# 09_FPGA_misc.net
KiCad netlist of a schematic drawn in Altium Designer
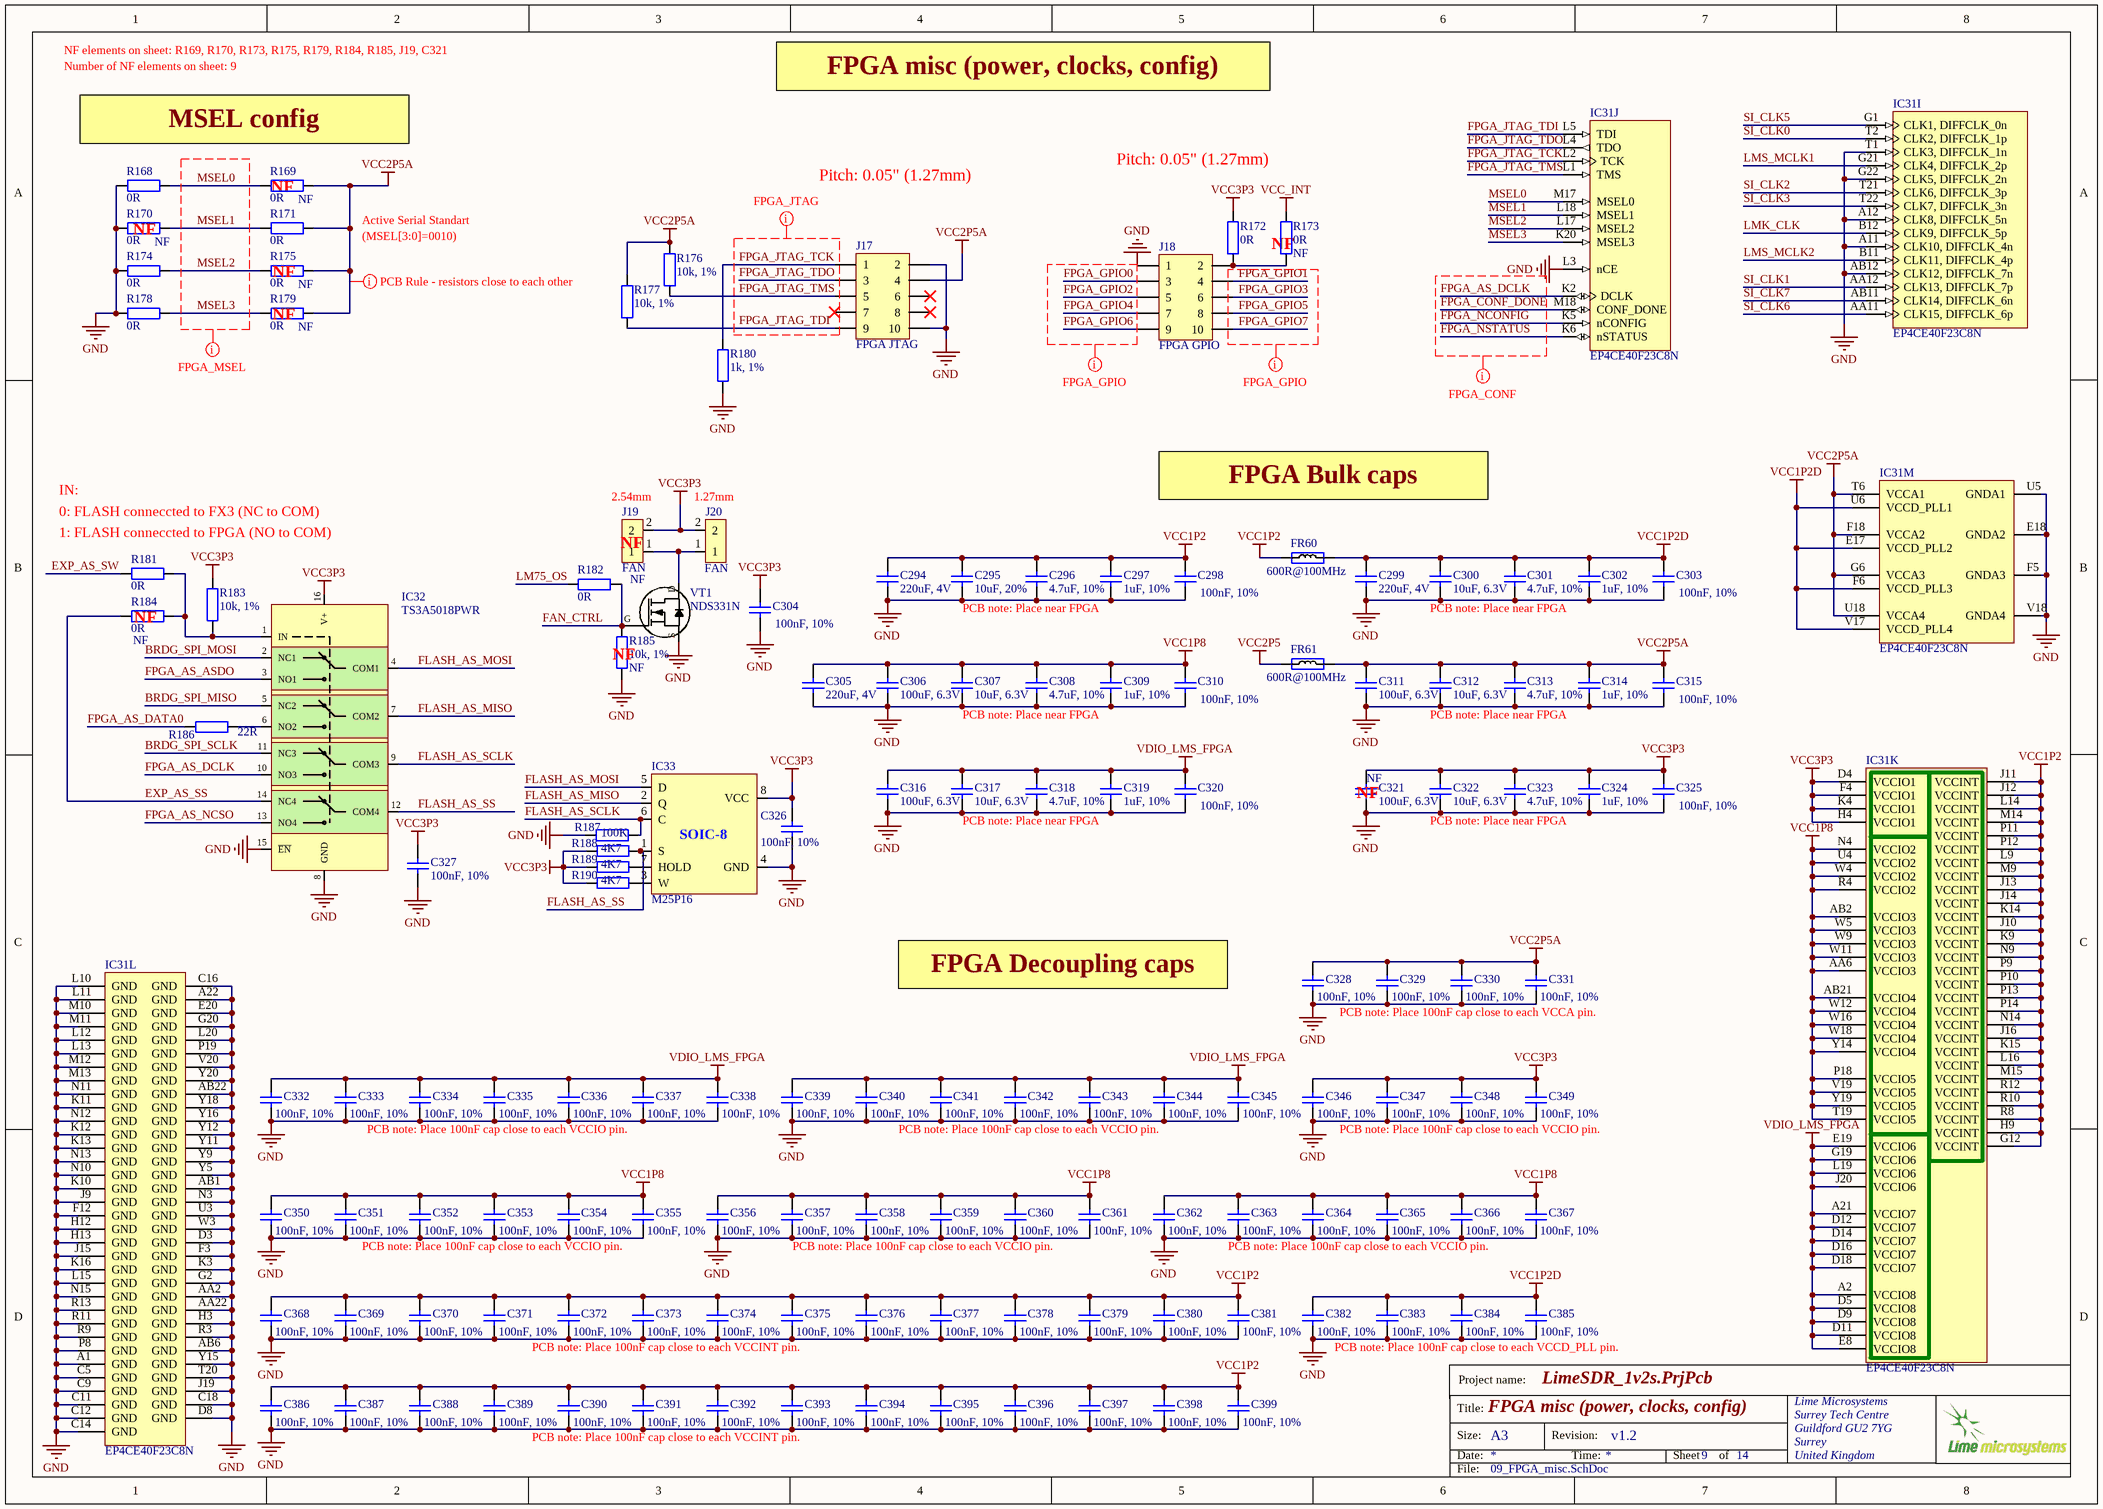
[diagram p0: 09_FPGA_misc.SchDoc]

(export (version "E")
  (design (tool "Eeschema 10.0.6"))
  (components
    (comp (ref "C294")
      (value "220uF, 4V")
      (footprint "LimeMicroAltiumLib_pcbLib:CAP1206")
      (fields
        (field (name "MANUFACTURER PART NUMBER") "GRM31CR60G227ME11L")
        (field (name "MANUFACTURER") "Murata Electronics North America")
        (field (name "TOLERANCE") "±20%")
      )
      (libsource (lib "LimeFPGAboard_schLib") (part "Cap_1206"))
    )
    (comp (ref "C295")
      (value "10uF, 20%")
      (footprint "CAP0603")
      (fields (field (name "MANUFACTURER") "Yageo") (field (name "TOLERANCE") "±20%"))
      (libsource (lib "LimeMicroAltiumLib_schLib") (part "Cap_0603"))
    )
    (comp (ref "C296")
      (value "4.7uF, 10%")
      (footprint "CAP0603")
      (fields (field (name "TOLERANCE") "10 %"))
      (libsource (lib "LimeFPGAboard_schLib") (part "Cap_0603"))
    )
    (comp (ref "C297")
      (value "1uF, 10%")
      (footprint "CAP0402")
      (fields (field (name "MANUFACTURER") "TDK"))
      (libsource (lib "LimeMicroAltiumLib_schLib") (part "Cap_0402"))
    )
    (comp (ref "C298")
      (value "100nF, 10%")
      (footprint "CAP0402")
      (fields
        (field (name "TOLERANCE") "10 %")
        (field (name "MANUFACTURER") "Murata Electronics")
        (field (name "MANUFACTURER PART NUMBER") "GRM155R71C104KA88D")
      )
      (libsource (lib "LimeFPGAboard_schLib") (part "Cap_0603"))
    )
    (comp (ref "C299")
      (value "220uF, 4V")
      (footprint "LimeMicroAltiumLib_pcbLib:CAP1206")
      (fields
        (field (name "MANUFACTURER PART NUMBER") "GRM31CR60G227ME11L")
        (field (name "MANUFACTURER") "Murata Electronics North America")
        (field (name "TOLERANCE") "±20%")
      )
      (libsource (lib "LimeFPGAboard_schLib") (part "Cap_1206"))
    )
    (comp (ref "C300")
      (value "10uF, 6.3V")
      (footprint "CAP0603")
      (fields (field (name "TOLERANCE") "±20%") (field (name "MANUFACTURER") "Yageo"))
      (libsource (lib "LimeFPGAboard_schLib") (part "Cap_0603"))
    )
    (comp (ref "C301")
      (value "4.7uF, 10%")
      (footprint "CAP0603")
      (fields (field (name "TOLERANCE") "10 %"))
      (libsource (lib "LimeFPGAboard_schLib") (part "Cap_0603"))
    )
    (comp (ref "C302")
      (value "1uF, 10%")
      (footprint "CAP0402")
      (fields (field (name "MANUFACTURER") "TDK"))
      (libsource (lib "LimeMicroAltiumLib_schLib") (part "Cap_0402"))
    )
    (comp (ref "C303")
      (value "100nF, 10%")
      (footprint "CAP0402")
      (fields
        (field (name "TOLERANCE") "10 %")
        (field (name "MANUFACTURER") "Murata Electronics")
        (field (name "MANUFACTURER PART NUMBER") "GRM155R71C104KA88D")
      )
      (libsource (lib "LimeFPGAboard_schLib") (part "Cap_0603"))
    )
    (comp (ref "C304")
      (value "100nF, 10%")
      (footprint "CAP0402")
      (fields
        (field (name "TOLERANCE") "10 %")
        (field (name "MANUFACTURER") "Murata Electronics")
        (field (name "MANUFACTURER PART NUMBER") "GRM155R71C104KA88D")
      )
      (libsource (lib "LimeFPGAboard_schLib") (part "Cap_0603"))
    )
    (comp (ref "C305")
      (value "220uF, 4V")
      (footprint "LimeMicroAltiumLib_pcbLib:CAP1206")
      (fields
        (field (name "MANUFACTURER PART NUMBER") "GRM31CR60G227ME11L")
        (field (name "MANUFACTURER") "Murata Electronics North America")
        (field (name "TOLERANCE") "±20%")
      )
      (libsource (lib "LimeFPGAboard_schLib") (part "Cap_1206"))
    )
    (comp (ref "C306")
      (value "100uF, 6.3V")
      (footprint "CAP1206")
      (fields (field (name "MANUFACTURER") "MURATA"))
      (libsource (lib "LimeFPGAboard_schLib") (part "Cap_1206"))
    )
    (comp (ref "C307")
      (value "10uF, 6.3V")
      (footprint "CAP0603")
      (fields (field (name "TOLERANCE") "±20%") (field (name "MANUFACTURER") "Yageo"))
      (libsource (lib "LimeFPGAboard_schLib") (part "Cap_0603"))
    )
    (comp (ref "C308")
      (value "4.7uF, 10%")
      (footprint "CAP0603")
      (fields (field (name "TOLERANCE") "10 %"))
      (libsource (lib "LimeFPGAboard_schLib") (part "Cap_0603"))
    )
    (comp (ref "C309")
      (value "1uF, 10%")
      (footprint "CAP0402")
      (fields (field (name "MANUFACTURER") "TDK"))
      (libsource (lib "LimeMicroAltiumLib_schLib") (part "Cap_0402"))
    )
    (comp (ref "C310")
      (value "100nF, 10%")
      (footprint "CAP0402")
      (fields
        (field (name "TOLERANCE") "10 %")
        (field (name "MANUFACTURER") "Murata Electronics")
        (field (name "MANUFACTURER PART NUMBER") "GRM155R71C104KA88D")
      )
      (libsource (lib "LimeFPGAboard_schLib") (part "Cap_0603"))
    )
    (comp (ref "C311")
      (value "100uF, 6.3V")
      (footprint "CAP1206")
      (fields (field (name "MANUFACTURER") "MURATA"))
      (libsource (lib "LimeFPGAboard_schLib") (part "Cap_1206"))
    )
    (comp (ref "C312")
      (value "10uF, 6.3V")
      (footprint "CAP0603")
      (fields (field (name "TOLERANCE") "±20%") (field (name "MANUFACTURER") "Yageo"))
      (libsource (lib "LimeFPGAboard_schLib") (part "Cap_0603"))
    )
    (comp (ref "C313")
      (value "4.7uF, 10%")
      (footprint "CAP0603")
      (fields (field (name "TOLERANCE") "10 %"))
      (libsource (lib "LimeFPGAboard_schLib") (part "Cap_0603"))
    )
    (comp (ref "C314")
      (value "1uF, 10%")
      (footprint "CAP0402")
      (fields (field (name "MANUFACTURER") "TDK"))
      (libsource (lib "LimeMicroAltiumLib_schLib") (part "Cap_0402"))
    )
    (comp (ref "C315")
      (value "100nF, 10%")
      (footprint "CAP0402")
      (fields
        (field (name "TOLERANCE") "10 %")
        (field (name "MANUFACTURER") "Murata Electronics")
        (field (name "MANUFACTURER PART NUMBER") "GRM155R71C104KA88D")
      )
      (libsource (lib "LimeFPGAboard_schLib") (part "Cap_0603"))
    )
    (comp (ref "C316")
      (value "100uF, 6.3V")
      (footprint "CAP1206")
      (fields (field (name "MANUFACTURER") "MURATA"))
      (libsource (lib "LimeFPGAboard_schLib") (part "Cap_1206"))
    )
    (comp (ref "C317")
      (value "10uF, 6.3V")
      (footprint "CAP0603")
      (fields (field (name "TOLERANCE") "±20%") (field (name "MANUFACTURER") "Yageo"))
      (libsource (lib "LimeFPGAboard_schLib") (part "Cap_0603"))
    )
    (comp (ref "C318")
      (value "4.7uF, 10%")
      (footprint "CAP0603")
      (fields (field (name "TOLERANCE") "10 %"))
      (libsource (lib "LimeFPGAboard_schLib") (part "Cap_0603"))
    )
    (comp (ref "C319")
      (value "1uF, 10%")
      (footprint "CAP0402")
      (fields (field (name "MANUFACTURER") "TDK"))
      (libsource (lib "LimeMicroAltiumLib_schLib") (part "Cap_0402"))
    )
    (comp (ref "C320")
      (value "100nF, 10%")
      (footprint "CAP0402")
      (fields
        (field (name "TOLERANCE") "10 %")
        (field (name "MANUFACTURER") "Murata Electronics")
        (field (name "MANUFACTURER PART NUMBER") "GRM155R71C104KA88D")
      )
      (libsource (lib "LimeFPGAboard_schLib") (part "Cap_0603"))
    )
    (comp (ref "C321")
      (value "100uF, 6.3V")
      (footprint "CAP1206")
      (fields (field (name "MANUFACTURER") "MURATA") (field (name "ASSEMBLY INFO") "NF"))
      (libsource (lib "LimeFPGAboard_schLib") (part "Cap_1206"))
    )
    (comp (ref "C322")
      (value "10uF, 6.3V")
      (footprint "CAP0603")
      (fields (field (name "TOLERANCE") "±20%") (field (name "MANUFACTURER") "Yageo"))
      (libsource (lib "LimeFPGAboard_schLib") (part "Cap_0603"))
    )
    (comp (ref "C323")
      (value "4.7uF, 10%")
      (footprint "CAP0603")
      (fields (field (name "TOLERANCE") "10 %"))
      (libsource (lib "LimeFPGAboard_schLib") (part "Cap_0603"))
    )
    (comp (ref "C324")
      (value "1uF, 10%")
      (footprint "CAP0402")
      (fields (field (name "MANUFACTURER") "TDK"))
      (libsource (lib "LimeMicroAltiumLib_schLib") (part "Cap_0402"))
    )
    (comp (ref "C325")
      (value "100nF, 10%")
      (footprint "CAP0402")
      (fields
        (field (name "TOLERANCE") "10 %")
        (field (name "MANUFACTURER") "Murata Electronics")
        (field (name "MANUFACTURER PART NUMBER") "GRM155R71C104KA88D")
      )
      (libsource (lib "LimeFPGAboard_schLib") (part "Cap_0603"))
    )
    (comp (ref "C326")
      (value "100nF, 10%")
      (footprint "CAP0402")
      (fields
        (field (name "TOLERANCE") "10 %")
        (field (name "MANUFACTURER") "Murata Electronics")
        (field (name "MANUFACTURER PART NUMBER") "GRM155R71C104KA88D")
      )
      (libsource (lib "LimeFPGAboard_schLib") (part "Cap_0603"))
    )
    (comp (ref "C327")
      (value "100nF, 10%")
      (footprint "CAP0402")
      (fields
        (field (name "TOLERANCE") "10 %")
        (field (name "MANUFACTURER") "Murata Electronics")
        (field (name "MANUFACTURER PART NUMBER") "GRM155R71C104KA88D")
      )
      (libsource (lib "LimeFPGAboard_schLib") (part "Cap_0603"))
    )
    (comp (ref "C328")
      (value "100nF, 10%")
      (footprint "CAP0402")
      (fields
        (field (name "TOLERANCE") "10 %")
        (field (name "MANUFACTURER") "Murata Electronics")
        (field (name "MANUFACTURER PART NUMBER") "GRM155R71C104KA88D")
      )
      (libsource (lib "LimeFPGAboard_schLib") (part "Cap_0603"))
    )
    (comp (ref "C329")
      (value "100nF, 10%")
      (footprint "CAP0402")
      (fields
        (field (name "TOLERANCE") "10 %")
        (field (name "MANUFACTURER") "Murata Electronics")
        (field (name "MANUFACTURER PART NUMBER") "GRM155R71C104KA88D")
      )
      (libsource (lib "LimeFPGAboard_schLib") (part "Cap_0603"))
    )
    (comp (ref "C330")
      (value "100nF, 10%")
      (footprint "CAP0402")
      (fields
        (field (name "TOLERANCE") "10 %")
        (field (name "MANUFACTURER") "Murata Electronics")
        (field (name "MANUFACTURER PART NUMBER") "GRM155R71C104KA88D")
      )
      (libsource (lib "LimeFPGAboard_schLib") (part "Cap_0603"))
    )
    (comp (ref "C331")
      (value "100nF, 10%")
      (footprint "CAP0402")
      (fields
        (field (name "TOLERANCE") "10 %")
        (field (name "MANUFACTURER") "Murata Electronics")
        (field (name "MANUFACTURER PART NUMBER") "GRM155R71C104KA88D")
      )
      (libsource (lib "LimeFPGAboard_schLib") (part "Cap_0603"))
    )
    (comp (ref "C332")
      (value "100nF, 10%")
      (footprint "CAP0402")
      (fields
        (field (name "TOLERANCE") "10 %")
        (field (name "MANUFACTURER") "Murata Electronics")
        (field (name "MANUFACTURER PART NUMBER") "GRM155R71C104KA88D")
      )
      (libsource (lib "LimeFPGAboard_schLib") (part "Cap_0603"))
    )
    (comp (ref "C333")
      (value "100nF, 10%")
      (footprint "CAP0402")
      (fields
        (field (name "TOLERANCE") "10 %")
        (field (name "MANUFACTURER") "Murata Electronics")
        (field (name "MANUFACTURER PART NUMBER") "GRM155R71C104KA88D")
      )
      (libsource (lib "LimeFPGAboard_schLib") (part "Cap_0603"))
    )
    (comp (ref "C334")
      (value "100nF, 10%")
      (footprint "CAP0402")
      (fields
        (field (name "TOLERANCE") "10 %")
        (field (name "MANUFACTURER") "Murata Electronics")
        (field (name "MANUFACTURER PART NUMBER") "GRM155R71C104KA88D")
      )
      (libsource (lib "LimeFPGAboard_schLib") (part "Cap_0603"))
    )
    (comp (ref "C335")
      (value "100nF, 10%")
      (footprint "CAP0402")
      (fields
        (field (name "TOLERANCE") "10 %")
        (field (name "MANUFACTURER") "Murata Electronics")
        (field (name "MANUFACTURER PART NUMBER") "GRM155R71C104KA88D")
      )
      (libsource (lib "LimeFPGAboard_schLib") (part "Cap_0603"))
    )
    (comp (ref "C336")
      (value "100nF, 10%")
      (footprint "CAP0402")
      (fields
        (field (name "TOLERANCE") "10 %")
        (field (name "MANUFACTURER") "Murata Electronics")
        (field (name "MANUFACTURER PART NUMBER") "GRM155R71C104KA88D")
      )
      (libsource (lib "LimeFPGAboard_schLib") (part "Cap_0603"))
    )
    (comp (ref "C337")
      (value "100nF, 10%")
      (footprint "CAP0402")
      (fields
        (field (name "TOLERANCE") "10 %")
        (field (name "MANUFACTURER") "Murata Electronics")
        (field (name "MANUFACTURER PART NUMBER") "GRM155R71C104KA88D")
      )
      (libsource (lib "LimeFPGAboard_schLib") (part "Cap_0603"))
    )
    (comp (ref "C338")
      (value "100nF, 10%")
      (footprint "CAP0402")
      (fields
        (field (name "TOLERANCE") "10 %")
        (field (name "MANUFACTURER") "Murata Electronics")
        (field (name "MANUFACTURER PART NUMBER") "GRM155R71C104KA88D")
      )
      (libsource (lib "LimeFPGAboard_schLib") (part "Cap_0603"))
    )
    (comp (ref "C339")
      (value "100nF, 10%")
      (footprint "CAP0402")
      (fields
        (field (name "TOLERANCE") "10 %")
        (field (name "MANUFACTURER") "Murata Electronics")
        (field (name "MANUFACTURER PART NUMBER") "GRM155R71C104KA88D")
      )
      (libsource (lib "LimeFPGAboard_schLib") (part "Cap_0603"))
    )
    (comp (ref "C340")
      (value "100nF, 10%")
      (footprint "CAP0402")
      (fields
        (field (name "TOLERANCE") "10 %")
        (field (name "MANUFACTURER") "Murata Electronics")
        (field (name "MANUFACTURER PART NUMBER") "GRM155R71C104KA88D")
      )
      (libsource (lib "LimeFPGAboard_schLib") (part "Cap_0603"))
    )
    (comp (ref "C341")
      (value "100nF, 10%")
      (footprint "CAP0402")
      (fields
        (field (name "TOLERANCE") "10 %")
        (field (name "MANUFACTURER") "Murata Electronics")
        (field (name "MANUFACTURER PART NUMBER") "GRM155R71C104KA88D")
      )
      (libsource (lib "LimeFPGAboard_schLib") (part "Cap_0603"))
    )
    (comp (ref "C342")
      (value "100nF, 10%")
      (footprint "CAP0402")
      (fields
        (field (name "TOLERANCE") "10 %")
        (field (name "MANUFACTURER") "Murata Electronics")
        (field (name "MANUFACTURER PART NUMBER") "GRM155R71C104KA88D")
      )
      (libsource (lib "LimeFPGAboard_schLib") (part "Cap_0603"))
    )
    (comp (ref "C343")
      (value "100nF, 10%")
      (footprint "CAP0402")
      (fields
        (field (name "TOLERANCE") "10 %")
        (field (name "MANUFACTURER") "Murata Electronics")
        (field (name "MANUFACTURER PART NUMBER") "GRM155R71C104KA88D")
      )
      (libsource (lib "LimeFPGAboard_schLib") (part "Cap_0603"))
    )
    (comp (ref "C344")
      (value "100nF, 10%")
      (footprint "CAP0402")
      (fields
        (field (name "TOLERANCE") "10 %")
        (field (name "MANUFACTURER") "Murata Electronics")
        (field (name "MANUFACTURER PART NUMBER") "GRM155R71C104KA88D")
      )
      (libsource (lib "LimeFPGAboard_schLib") (part "Cap_0603"))
    )
    (comp (ref "C345")
      (value "100nF, 10%")
      (footprint "CAP0402")
      (fields
        (field (name "TOLERANCE") "10 %")
        (field (name "MANUFACTURER") "Murata Electronics")
        (field (name "MANUFACTURER PART NUMBER") "GRM155R71C104KA88D")
      )
      (libsource (lib "LimeFPGAboard_schLib") (part "Cap_0603"))
    )
    (comp (ref "C346")
      (value "100nF, 10%")
      (footprint "CAP0402")
      (fields
        (field (name "TOLERANCE") "10 %")
        (field (name "MANUFACTURER") "Murata Electronics")
        (field (name "MANUFACTURER PART NUMBER") "GRM155R71C104KA88D")
      )
      (libsource (lib "LimeFPGAboard_schLib") (part "Cap_0603"))
    )
    (comp (ref "C347")
      (value "100nF, 10%")
      (footprint "CAP0402")
      (fields
        (field (name "TOLERANCE") "10 %")
        (field (name "MANUFACTURER") "Murata Electronics")
        (field (name "MANUFACTURER PART NUMBER") "GRM155R71C104KA88D")
      )
      (libsource (lib "LimeFPGAboard_schLib") (part "Cap_0603"))
    )
    (comp (ref "C348")
      (value "100nF, 10%")
      (footprint "CAP0402")
      (fields
        (field (name "TOLERANCE") "10 %")
        (field (name "MANUFACTURER") "Murata Electronics")
        (field (name "MANUFACTURER PART NUMBER") "GRM155R71C104KA88D")
      )
      (libsource (lib "LimeFPGAboard_schLib") (part "Cap_0603"))
    )
    (comp (ref "C349")
      (value "100nF, 10%")
      (footprint "CAP0402")
      (fields
        (field (name "TOLERANCE") "10 %")
        (field (name "MANUFACTURER") "Murata Electronics")
        (field (name "MANUFACTURER PART NUMBER") "GRM155R71C104KA88D")
      )
      (libsource (lib "LimeFPGAboard_schLib") (part "Cap_0603"))
    )
    (comp (ref "C350")
      (value "100nF, 10%")
      (footprint "CAP0402")
      (fields
        (field (name "TOLERANCE") "10 %")
        (field (name "MANUFACTURER") "Murata Electronics")
        (field (name "MANUFACTURER PART NUMBER") "GRM155R71C104KA88D")
      )
      (libsource (lib "LimeFPGAboard_schLib") (part "Cap_0603"))
    )
    (comp (ref "C351")
      (value "100nF, 10%")
      (footprint "CAP0402")
      (fields
        (field (name "TOLERANCE") "10 %")
        (field (name "MANUFACTURER") "Murata Electronics")
        (field (name "MANUFACTURER PART NUMBER") "GRM155R71C104KA88D")
      )
      (libsource (lib "LimeFPGAboard_schLib") (part "Cap_0603"))
    )
    (comp (ref "C352")
      (value "100nF, 10%")
      (footprint "CAP0402")
      (fields
        (field (name "TOLERANCE") "10 %")
        (field (name "MANUFACTURER") "Murata Electronics")
        (field (name "MANUFACTURER PART NUMBER") "GRM155R71C104KA88D")
      )
      (libsource (lib "LimeFPGAboard_schLib") (part "Cap_0603"))
    )
    (comp (ref "C353")
      (value "100nF, 10%")
      (footprint "CAP0402")
      (fields
        (field (name "TOLERANCE") "10 %")
        (field (name "MANUFACTURER") "Murata Electronics")
        (field (name "MANUFACTURER PART NUMBER") "GRM155R71C104KA88D")
      )
      (libsource (lib "LimeFPGAboard_schLib") (part "Cap_0603"))
    )
    (comp (ref "C354")
      (value "100nF, 10%")
      (footprint "CAP0402")
      (fields
        (field (name "TOLERANCE") "10 %")
        (field (name "MANUFACTURER") "Murata Electronics")
        (field (name "MANUFACTURER PART NUMBER") "GRM155R71C104KA88D")
      )
      (libsource (lib "LimeFPGAboard_schLib") (part "Cap_0603"))
    )
    (comp (ref "C355")
      (value "100nF, 10%")
      (footprint "CAP0402")
      (fields
        (field (name "TOLERANCE") "10 %")
        (field (name "MANUFACTURER") "Murata Electronics")
        (field (name "MANUFACTURER PART NUMBER") "GRM155R71C104KA88D")
      )
      (libsource (lib "LimeFPGAboard_schLib") (part "Cap_0603"))
    )
    (comp (ref "C356")
      (value "100nF, 10%")
      (footprint "CAP0402")
      (fields
        (field (name "TOLERANCE") "10 %")
        (field (name "MANUFACTURER") "Murata Electronics")
        (field (name "MANUFACTURER PART NUMBER") "GRM155R71C104KA88D")
      )
      (libsource (lib "LimeFPGAboard_schLib") (part "Cap_0603"))
    )
    (comp (ref "C357")
      (value "100nF, 10%")
      (footprint "CAP0402")
      (fields
        (field (name "TOLERANCE") "10 %")
        (field (name "MANUFACTURER") "Murata Electronics")
        (field (name "MANUFACTURER PART NUMBER") "GRM155R71C104KA88D")
      )
      (libsource (lib "LimeFPGAboard_schLib") (part "Cap_0603"))
    )
    (comp (ref "C358")
      (value "100nF, 10%")
      (footprint "CAP0402")
      (fields
        (field (name "TOLERANCE") "10 %")
        (field (name "MANUFACTURER") "Murata Electronics")
        (field (name "MANUFACTURER PART NUMBER") "GRM155R71C104KA88D")
      )
      (libsource (lib "LimeFPGAboard_schLib") (part "Cap_0603"))
    )
    (comp (ref "C359")
      (value "100nF, 10%")
      (footprint "CAP0402")
      (fields
        (field (name "TOLERANCE") "10 %")
        (field (name "MANUFACTURER") "Murata Electronics")
        (field (name "MANUFACTURER PART NUMBER") "GRM155R71C104KA88D")
      )
      (libsource (lib "LimeFPGAboard_schLib") (part "Cap_0603"))
    )
    (comp (ref "C360")
      (value "100nF, 10%")
      (footprint "CAP0402")
      (fields
        (field (name "TOLERANCE") "10 %")
        (field (name "MANUFACTURER") "Murata Electronics")
        (field (name "MANUFACTURER PART NUMBER") "GRM155R71C104KA88D")
      )
      (libsource (lib "LimeFPGAboard_schLib") (part "Cap_0603"))
    )
    (comp (ref "C361")
      (value "100nF, 10%")
      (footprint "CAP0402")
      (fields
        (field (name "TOLERANCE") "10 %")
        (field (name "MANUFACTURER") "Murata Electronics")
        (field (name "MANUFACTURER PART NUMBER") "GRM155R71C104KA88D")
      )
      (libsource (lib "LimeFPGAboard_schLib") (part "Cap_0603"))
    )
    (comp (ref "C362")
      (value "100nF, 10%")
      (footprint "CAP0402")
      (fields
        (field (name "TOLERANCE") "10 %")
        (field (name "MANUFACTURER") "Murata Electronics")
        (field (name "MANUFACTURER PART NUMBER") "GRM155R71C104KA88D")
      )
      (libsource (lib "LimeFPGAboard_schLib") (part "Cap_0603"))
    )
    (comp (ref "C363")
      (value "100nF, 10%")
      (footprint "CAP0402")
      (fields
        (field (name "TOLERANCE") "10 %")
        (field (name "MANUFACTURER") "Murata Electronics")
        (field (name "MANUFACTURER PART NUMBER") "GRM155R71C104KA88D")
      )
      (libsource (lib "LimeFPGAboard_schLib") (part "Cap_0603"))
    )
    (comp (ref "C364")
      (value "100nF, 10%")
      (footprint "CAP0402")
      (fields
        (field (name "TOLERANCE") "10 %")
        (field (name "MANUFACTURER") "Murata Electronics")
        (field (name "MANUFACTURER PART NUMBER") "GRM155R71C104KA88D")
      )
      (libsource (lib "LimeFPGAboard_schLib") (part "Cap_0603"))
    )
    (comp (ref "C365")
      (value "100nF, 10%")
      (footprint "CAP0402")
      (fields
        (field (name "TOLERANCE") "10 %")
        (field (name "MANUFACTURER") "Murata Electronics")
        (field (name "MANUFACTURER PART NUMBER") "GRM155R71C104KA88D")
      )
      (libsource (lib "LimeFPGAboard_schLib") (part "Cap_0603"))
    )
    (comp (ref "C366")
      (value "100nF, 10%")
      (footprint "CAP0402")
      (fields
        (field (name "TOLERANCE") "10 %")
        (field (name "MANUFACTURER") "Murata Electronics")
        (field (name "MANUFACTURER PART NUMBER") "GRM155R71C104KA88D")
      )
      (libsource (lib "LimeFPGAboard_schLib") (part "Cap_0603"))
    )
    (comp (ref "C367")
      (value "100nF, 10%")
      (footprint "CAP0402")
      (fields
        (field (name "TOLERANCE") "10 %")
        (field (name "MANUFACTURER") "Murata Electronics")
        (field (name "MANUFACTURER PART NUMBER") "GRM155R71C104KA88D")
      )
      (libsource (lib "LimeFPGAboard_schLib") (part "Cap_0603"))
    )
    (comp (ref "C368")
      (value "100nF, 10%")
      (footprint "CAP0402")
      (fields
        (field (name "TOLERANCE") "10 %")
        (field (name "MANUFACTURER") "Murata Electronics")
        (field (name "MANUFACTURER PART NUMBER") "GRM155R71C104KA88D")
      )
      (libsource (lib "LimeFPGAboard_schLib") (part "Cap_0603"))
    )
    (comp (ref "C369")
      (value "100nF, 10%")
      (footprint "CAP0402")
      (fields
        (field (name "TOLERANCE") "10 %")
        (field (name "MANUFACTURER") "Murata Electronics")
        (field (name "MANUFACTURER PART NUMBER") "GRM155R71C104KA88D")
      )
      (libsource (lib "LimeFPGAboard_schLib") (part "Cap_0603"))
    )
    (comp (ref "C370")
      (value "100nF, 10%")
      (footprint "CAP0402")
      (fields
        (field (name "TOLERANCE") "10 %")
        (field (name "MANUFACTURER") "Murata Electronics")
        (field (name "MANUFACTURER PART NUMBER") "GRM155R71C104KA88D")
      )
      (libsource (lib "LimeFPGAboard_schLib") (part "Cap_0603"))
    )
    (comp (ref "C371")
      (value "100nF, 10%")
      (footprint "CAP0402")
      (fields
        (field (name "TOLERANCE") "10 %")
        (field (name "MANUFACTURER") "Murata Electronics")
        (field (name "MANUFACTURER PART NUMBER") "GRM155R71C104KA88D")
      )
      (libsource (lib "LimeFPGAboard_schLib") (part "Cap_0603"))
    )
    (comp (ref "C372")
      (value "100nF, 10%")
      (footprint "CAP0402")
      (fields
        (field (name "TOLERANCE") "10 %")
        (field (name "MANUFACTURER") "Murata Electronics")
        (field (name "MANUFACTURER PART NUMBER") "GRM155R71C104KA88D")
      )
      (libsource (lib "LimeFPGAboard_schLib") (part "Cap_0603"))
    )
    (comp (ref "C373")
      (value "100nF, 10%")
      (footprint "CAP0402")
      (fields
        (field (name "TOLERANCE") "10 %")
        (field (name "MANUFACTURER") "Murata Electronics")
        (field (name "MANUFACTURER PART NUMBER") "GRM155R71C104KA88D")
      )
      (libsource (lib "LimeFPGAboard_schLib") (part "Cap_0603"))
    )
    (comp (ref "C374")
      (value "100nF, 10%")
      (footprint "CAP0402")
      (fields
        (field (name "TOLERANCE") "10 %")
        (field (name "MANUFACTURER") "Murata Electronics")
        (field (name "MANUFACTURER PART NUMBER") "GRM155R71C104KA88D")
      )
      (libsource (lib "LimeFPGAboard_schLib") (part "Cap_0603"))
    )
    (comp (ref "C375")
      (value "100nF, 10%")
      (footprint "CAP0402")
      (fields
        (field (name "TOLERANCE") "10 %")
        (field (name "MANUFACTURER") "Murata Electronics")
        (field (name "MANUFACTURER PART NUMBER") "GRM155R71C104KA88D")
      )
      (libsource (lib "LimeFPGAboard_schLib") (part "Cap_0603"))
    )
    (comp (ref "C376")
      (value "100nF, 10%")
      (footprint "CAP0402")
      (fields
        (field (name "TOLERANCE") "10 %")
        (field (name "MANUFACTURER") "Murata Electronics")
        (field (name "MANUFACTURER PART NUMBER") "GRM155R71C104KA88D")
      )
      (libsource (lib "LimeFPGAboard_schLib") (part "Cap_0603"))
    )
    (comp (ref "C377")
      (value "100nF, 10%")
      (footprint "CAP0402")
      (fields
        (field (name "TOLERANCE") "10 %")
        (field (name "MANUFACTURER") "Murata Electronics")
        (field (name "MANUFACTURER PART NUMBER") "GRM155R71C104KA88D")
      )
      (libsource (lib "LimeFPGAboard_schLib") (part "Cap_0603"))
    )
    (comp (ref "C378")
      (value "100nF, 10%")
      (footprint "CAP0402")
      (fields
        (field (name "TOLERANCE") "10 %")
        (field (name "MANUFACTURER") "Murata Electronics")
        (field (name "MANUFACTURER PART NUMBER") "GRM155R71C104KA88D")
      )
      (libsource (lib "LimeFPGAboard_schLib") (part "Cap_0603"))
    )
    (comp (ref "C379")
      (value "100nF, 10%")
      (footprint "CAP0402")
      (fields
        (field (name "TOLERANCE") "10 %")
        (field (name "MANUFACTURER") "Murata Electronics")
        (field (name "MANUFACTURER PART NUMBER") "GRM155R71C104KA88D")
      )
      (libsource (lib "LimeFPGAboard_schLib") (part "Cap_0603"))
    )
    (comp (ref "C380")
      (value "100nF, 10%")
      (footprint "CAP0402")
      (fields
        (field (name "TOLERANCE") "10 %")
        (field (name "MANUFACTURER") "Murata Electronics")
        (field (name "MANUFACTURER PART NUMBER") "GRM155R71C104KA88D")
      )
      (libsource (lib "LimeFPGAboard_schLib") (part "Cap_0603"))
    )
    (comp (ref "C381")
      (value "100nF, 10%")
      (footprint "CAP0402")
      (fields
        (field (name "TOLERANCE") "10 %")
        (field (name "MANUFACTURER") "Murata Electronics")
        (field (name "MANUFACTURER PART NUMBER") "GRM155R71C104KA88D")
      )
      (libsource (lib "LimeFPGAboard_schLib") (part "Cap_0603"))
    )
    (comp (ref "C382")
      (value "100nF, 10%")
      (footprint "CAP0402")
      (fields
        (field (name "TOLERANCE") "10 %")
        (field (name "MANUFACTURER") "Murata Electronics")
        (field (name "MANUFACTURER PART NUMBER") "GRM155R71C104KA88D")
      )
      (libsource (lib "LimeFPGAboard_schLib") (part "Cap_0603"))
    )
    (comp (ref "C383")
      (value "100nF, 10%")
      (footprint "CAP0402")
      (fields
        (field (name "TOLERANCE") "10 %")
        (field (name "MANUFACTURER") "Murata Electronics")
        (field (name "MANUFACTURER PART NUMBER") "GRM155R71C104KA88D")
      )
      (libsource (lib "LimeFPGAboard_schLib") (part "Cap_0603"))
    )
    (comp (ref "C384")
      (value "100nF, 10%")
      (footprint "CAP0402")
      (fields
        (field (name "TOLERANCE") "10 %")
        (field (name "MANUFACTURER") "Murata Electronics")
        (field (name "MANUFACTURER PART NUMBER") "GRM155R71C104KA88D")
      )
      (libsource (lib "LimeFPGAboard_schLib") (part "Cap_0603"))
    )
    (comp (ref "C385")
      (value "100nF, 10%")
      (footprint "CAP0402")
      (fields
        (field (name "TOLERANCE") "10 %")
        (field (name "MANUFACTURER") "Murata Electronics")
        (field (name "MANUFACTURER PART NUMBER") "GRM155R71C104KA88D")
      )
      (libsource (lib "LimeFPGAboard_schLib") (part "Cap_0603"))
    )
    (comp (ref "C386")
      (value "100nF, 10%")
      (footprint "CAP0402")
      (fields
        (field (name "TOLERANCE") "10 %")
        (field (name "MANUFACTURER") "Murata Electronics")
        (field (name "MANUFACTURER PART NUMBER") "GRM155R71C104KA88D")
      )
      (libsource (lib "LimeFPGAboard_schLib") (part "Cap_0603"))
    )
    (comp (ref "C387")
      (value "100nF, 10%")
      (footprint "CAP0402")
      (fields
        (field (name "TOLERANCE") "10 %")
        (field (name "MANUFACTURER") "Murata Electronics")
        (field (name "MANUFACTURER PART NUMBER") "GRM155R71C104KA88D")
      )
      (libsource (lib "LimeFPGAboard_schLib") (part "Cap_0603"))
    )
    (comp (ref "C388")
      (value "100nF, 10%")
      (footprint "CAP0402")
      (fields
        (field (name "TOLERANCE") "10 %")
        (field (name "MANUFACTURER") "Murata Electronics")
        (field (name "MANUFACTURER PART NUMBER") "GRM155R71C104KA88D")
      )
      (libsource (lib "LimeFPGAboard_schLib") (part "Cap_0603"))
    )
    (comp (ref "C389")
      (value "100nF, 10%")
      (footprint "CAP0402")
      (fields
        (field (name "TOLERANCE") "10 %")
        (field (name "MANUFACTURER") "Murata Electronics")
        (field (name "MANUFACTURER PART NUMBER") "GRM155R71C104KA88D")
      )
      (libsource (lib "LimeFPGAboard_schLib") (part "Cap_0603"))
    )
    (comp (ref "C390")
      (value "100nF, 10%")
      (footprint "CAP0402")
      (fields
        (field (name "TOLERANCE") "10 %")
        (field (name "MANUFACTURER") "Murata Electronics")
        (field (name "MANUFACTURER PART NUMBER") "GRM155R71C104KA88D")
      )
      (libsource (lib "LimeFPGAboard_schLib") (part "Cap_0603"))
    )
    (comp (ref "C391")
      (value "100nF, 10%")
      (footprint "CAP0402")
      (fields
        (field (name "TOLERANCE") "10 %")
        (field (name "MANUFACTURER") "Murata Electronics")
        (field (name "MANUFACTURER PART NUMBER") "GRM155R71C104KA88D")
      )
      (libsource (lib "LimeFPGAboard_schLib") (part "Cap_0603"))
    )
    (comp (ref "C392")
      (value "100nF, 10%")
      (footprint "CAP0402")
      (fields
        (field (name "TOLERANCE") "10 %")
        (field (name "MANUFACTURER") "Murata Electronics")
        (field (name "MANUFACTURER PART NUMBER") "GRM155R71C104KA88D")
      )
      (libsource (lib "LimeFPGAboard_schLib") (part "Cap_0603"))
    )
    (comp (ref "C393")
      (value "100nF, 10%")
      (footprint "CAP0402")
      (fields
        (field (name "TOLERANCE") "10 %")
        (field (name "MANUFACTURER") "Murata Electronics")
        (field (name "MANUFACTURER PART NUMBER") "GRM155R71C104KA88D")
      )
      (libsource (lib "LimeFPGAboard_schLib") (part "Cap_0603"))
    )
    (comp (ref "C394")
      (value "100nF, 10%")
      (footprint "CAP0402")
      (fields
        (field (name "TOLERANCE") "10 %")
        (field (name "MANUFACTURER") "Murata Electronics")
        (field (name "MANUFACTURER PART NUMBER") "GRM155R71C104KA88D")
      )
      (libsource (lib "LimeFPGAboard_schLib") (part "Cap_0603"))
    )
    (comp (ref "C395")
      (value "100nF, 10%")
      (footprint "CAP0402")
      (fields
        (field (name "TOLERANCE") "10 %")
        (field (name "MANUFACTURER") "Murata Electronics")
        (field (name "MANUFACTURER PART NUMBER") "GRM155R71C104KA88D")
      )
      (libsource (lib "LimeFPGAboard_schLib") (part "Cap_0603"))
    )
    (comp (ref "C396")
      (value "100nF, 10%")
      (footprint "CAP0402")
      (fields
        (field (name "TOLERANCE") "10 %")
        (field (name "MANUFACTURER") "Murata Electronics")
        (field (name "MANUFACTURER PART NUMBER") "GRM155R71C104KA88D")
      )
      (libsource (lib "LimeFPGAboard_schLib") (part "Cap_0603"))
    )
    (comp (ref "C397")
      (value "100nF, 10%")
      (footprint "CAP0402")
      (fields
        (field (name "TOLERANCE") "10 %")
        (field (name "MANUFACTURER") "Murata Electronics")
        (field (name "MANUFACTURER PART NUMBER") "GRM155R71C104KA88D")
      )
      (libsource (lib "LimeFPGAboard_schLib") (part "Cap_0603"))
    )
    (comp (ref "C398")
      (value "100nF, 10%")
      (footprint "CAP0402")
      (fields
        (field (name "TOLERANCE") "10 %")
        (field (name "MANUFACTURER") "Murata Electronics")
        (field (name "MANUFACTURER PART NUMBER") "GRM155R71C104KA88D")
      )
      (libsource (lib "LimeFPGAboard_schLib") (part "Cap_0603"))
    )
    (comp (ref "C399")
      (value "100nF, 10%")
      (footprint "CAP0402")
      (fields
        (field (name "TOLERANCE") "10 %")
        (field (name "MANUFACTURER") "Murata Electronics")
        (field (name "MANUFACTURER PART NUMBER") "GRM155R71C104KA88D")
      )
      (libsource (lib "LimeFPGAboard_schLib") (part "Cap_0603"))
    )
    (comp (ref "FR60")
      (value "600R@100MHz")
      (footprint "RES0805")
      (fields (field (name "MANUFACTURER") "TDK Corporation"))
      (libsource (lib "LimeMicroAltiumLib_schLib") (part "Ferrite"))
    )
    (comp (ref "FR61")
      (value "600R@100MHz")
      (footprint "RES0805")
      (fields (field (name "MANUFACTURER") "TDK Corporation"))
      (libsource (lib "LimeMicroAltiumLib_schLib") (part "Ferrite"))
    )
    (comp (ref "IC31")
      (value "EP4CE40F23C8N")
      (footprint "FBGA484_A-240")
      (description "IC FPGA 328 I/O 484FBGA")
      (fields (field (name "MANUFACTURER") "Altera"))
      (libsource (lib "LimeMicroAltiumLib_schLib") (part "EP4CE40F23C7N"))
    )
    (comp (ref "IC32")
      (value "TS3A5018PWR")
      (footprint "TS3A5018PWR")
      (fields (field (name "MANUFACTURER") "TEXAS INSTRUMENTS"))
      (libsource (lib "LimeFPGAboard_schLib") (part "TS3A5018PWR"))
    )
    (comp (ref "IC33")
      (value "M25P16")
      (footprint "M25P40-VMN6TPB_SO8N")
      (fields (field (name "MANUFACTURER") "Micron Technology Inc."))
      (libsource (lib "LimeFPGAboard_schLib") (part "M25P40"))
    )
    (comp (ref "J17")
      (value "FPGA JTAG")
      (footprint "SWD_10_pin")
      (description "Header, 5-Pin, Dual row")
      (fields (field (name "MANUFACTURER") "Harwin Inc"))
      (libsource (lib "LimeMicroAltiumLib_schLib") (part "Header 5X2_SWD"))
    )
    (comp (ref "J18")
      (value "FPGA GPIO")
      (footprint "SWD_10_pin")
      (description "Header, 5-Pin, Dual row")
      (fields (field (name "MANUFACTURER") "Harwin Inc"))
      (libsource (lib "LimeMicroAltiumLib_schLib") (part "Header 5X2_SWD"))
    )
    (comp (ref "J19")
      (value "FAN")
      (footprint "LimeMicroAltiumLib_pcbLib:HDR_1x2")
      (fields (field (name "ASSEMBLY INFO") "NF"))
      (libsource (lib "") (part "Jumper_1"))
    )
    (comp (ref "J20")
      (value "FAN")
      (footprint "HDR_1x2_HALF_PITCH")
      (fields (field (name "MANUFACTURER") "Sullins Connector Solutions"))
      (libsource (lib "LimeFPGAboard_schLib") (part "Jumper"))
    )
    (comp (ref "R168")
      (value "0R")
      (footprint "RES0402")
      (fields (field (name "MANUFACTURER") "Yageo"))
      (libsource (lib "LimeFPGAboard_schLib") (part "Res_0402"))
    )
    (comp (ref "R169")
      (value "0R")
      (footprint "RES0402")
      (fields (field (name "MANUFACTURER") "Yageo") (field (name "ASSEMBLY INFO") "NF"))
      (libsource (lib "LimeFPGAboard_schLib") (part "Res_0402"))
    )
    (comp (ref "R170")
      (value "0R")
      (footprint "RES0402")
      (fields (field (name "MANUFACTURER") "Yageo") (field (name "ASSEMBLY INFO") "NF"))
      (libsource (lib "LimeFPGAboard_schLib") (part "Res_0402"))
    )
    (comp (ref "R171")
      (value "0R")
      (footprint "RES0402")
      (fields (field (name "MANUFACTURER") "Yageo"))
      (libsource (lib "LimeFPGAboard_schLib") (part "Res_0402"))
    )
    (comp (ref "R172")
      (value "0R")
      (footprint "RES0402")
      (fields (field (name "MANUFACTURER") "Yageo"))
      (libsource (lib "LimeFPGAboard_schLib") (part "Res_0402"))
    )
    (comp (ref "R173")
      (value "0R")
      (footprint "RES0402")
      (fields (field (name "MANUFACTURER") "Yageo") (field (name "ASSEMBLY INFO") "NF"))
      (libsource (lib "LimeFPGAboard_schLib") (part "Res_0402"))
    )
    (comp (ref "R174")
      (value "0R")
      (footprint "RES0402")
      (fields (field (name "MANUFACTURER") "Yageo"))
      (libsource (lib "LimeFPGAboard_schLib") (part "Res_0402"))
    )
    (comp (ref "R175")
      (value "0R")
      (footprint "RES0402")
      (fields (field (name "MANUFACTURER") "Yageo") (field (name "ASSEMBLY INFO") "NF"))
      (libsource (lib "LimeFPGAboard_schLib") (part "Res_0402"))
    )
    (comp (ref "R176")
      (value "10k, 1%")
      (footprint "RES0402")
      (fields (field (name "MANUFACTURER") "Yageo") (field (name "TOLERANCE") "±1%"))
      (libsource (lib "LimeMicroAltiumLib_schLib") (part "Res_0402"))
    )
    (comp (ref "R177")
      (value "10k, 1%")
      (footprint "RES0402")
      (fields (field (name "MANUFACTURER") "Yageo") (field (name "TOLERANCE") "±1%"))
      (libsource (lib "LimeMicroAltiumLib_schLib") (part "Res_0402"))
    )
    (comp (ref "R178")
      (value "0R")
      (footprint "RES0402")
      (fields (field (name "MANUFACTURER") "Yageo"))
      (libsource (lib "LimeFPGAboard_schLib") (part "Res_0402"))
    )
    (comp (ref "R179")
      (value "0R")
      (footprint "RES0402")
      (fields (field (name "MANUFACTURER") "Yageo") (field (name "ASSEMBLY INFO") "NF"))
      (libsource (lib "LimeFPGAboard_schLib") (part "Res_0402"))
    )
    (comp (ref "R180")
      (value "1k, 1%")
      (footprint "RES0402")
      (fields (field (name "MANUFACTURER") "Stackpole Electronics Inc") (field (name "TOLERANCE") "±1%"))
      (libsource (lib "LimeMicroAltiumLib_schLib") (part "Res_0402"))
    )
    (comp (ref "R181")
      (value "0R")
      (footprint "RES0402")
      (fields (field (name "MANUFACTURER") "Yageo"))
      (libsource (lib "LimeFPGAboard_schLib") (part "Res_0402"))
    )
    (comp (ref "R182")
      (value "0R")
      (footprint "RES0402")
      (fields (field (name "MANUFACTURER") "Yageo"))
      (libsource (lib "LimeFPGAboard_schLib") (part "Res_0402"))
    )
    (comp (ref "R183")
      (value "10k, 1%")
      (footprint "RES0402")
      (fields (field (name "MANUFACTURER") "Yageo") (field (name "TOLERANCE") "±1%"))
      (libsource (lib "LimeMicroAltiumLib_schLib") (part "Res_0402"))
    )
    (comp (ref "R184")
      (value "0R")
      (footprint "RES0402")
      (fields (field (name "MANUFACTURER") "Yageo") (field (name "ASSEMBLY INFO") "NF"))
      (libsource (lib "LimeFPGAboard_schLib") (part "Res_0402"))
    )
    (comp (ref "R185")
      (value "10k, 1%")
      (footprint "RES0402")
      (fields
        (field (name "ASSEMBLY INFO") "NF")
        (field (name "MANUFACTURER") "Yageo")
        (field (name "TOLERANCE") "±1%")
      )
      (libsource (lib "LimeMicroAltiumLib_schLib") (part "Res_0402"))
    )
    (comp (ref "R186")
      (value "22R")
      (footprint "RES0402")
      (fields (field (name "TOLERANCE") "±1%"))
      (libsource (lib "LimeFPGAboard_schLib") (part "Res_0402"))
    )
    (comp (ref "R187")
      (value "100K")
      (footprint "RES0402")
      (fields
        (field (name "TOLERANCE") "±5%")
        (field (name "MANUFACTURER") "Panasonic Electronic Components")
      )
      (libsource (lib "LimeFPGAboard_schLib") (part "Res_0402"))
    )
    (comp (ref "R188")
      (value "4K7")
      (footprint "RES0402")
      (fields (field (name "TOLERANCE") "±5%") (field (name "MANUFACTURER") "Stackpole Electronics Inc."))
      (libsource (lib "LimeFPGAboard_schLib") (part "Res_0402"))
    )
    (comp (ref "R189")
      (value "4K7")
      (footprint "RES0402")
      (fields (field (name "TOLERANCE") "±5%") (field (name "MANUFACTURER") "Stackpole Electronics Inc."))
      (libsource (lib "LimeFPGAboard_schLib") (part "Res_0402"))
    )
    (comp (ref "R190")
      (value "4K7")
      (footprint "RES0402")
      (fields (field (name "TOLERANCE") "±5%") (field (name "MANUFACTURER") "Stackpole Electronics Inc."))
      (libsource (lib "LimeFPGAboard_schLib") (part "Res_0402"))
    )
    (comp (ref "VT1")
      (value "NDS331N")
      (footprint "LimeMicroAltiumLib_pcbLib:SOT23-3")
      (fields (field (name "MANUFACTURER") "Fairchild Semiconductor"))
      (libsource (lib "LimeFPGAboard_schLib") (part "NDS331N"))
    )
  )
  (nets
    (net (code "1") (name "/BRDG_SPI_MISO") (class "Default")
      (node (ref "IC32") (pin "5") (pinfunction "NC2_5") (pintype "passive"))
    )
    (net (code "2") (name "/BRDG_SPI_MOSI") (class "Default")
      (node (ref "IC32") (pin "2") (pinfunction "NC1_2") (pintype "passive"))
    )
    (net (code "3") (name "/BRDG_SPI_SCLK") (class "Default")
      (node (ref "IC32") (pin "11") (pinfunction "NC3_11") (pintype "passive"))
    )
    (net (code "4") (name "/EXP_AS_SS") (class "Default")
      (node (ref "IC32") (pin "14") (pinfunction "NC4_14") (pintype "passive"))
      (node (ref "R184") (pin "2") (pinfunction "2_2") (pintype "passive"))
    )
    (net (code "5") (name "/EXP_AS_SW") (class "Default")
      (node (ref "R181") (pin "2") (pinfunction "2_2") (pintype "passive"))
    )
    (net (code "6") (name "/FAN_CTRL") (class "Default")
      (node (ref "R182") (pin "2") (pinfunction "2_2") (pintype "passive"))
      (node (ref "R185") (pin "1") (pinfunction "1_1") (pintype "passive"))
      (node (ref "VT1") (pin "G") (pinfunction "G_G") (pintype "passive"))
    )
    (net (code "7") (name "/FLASH_AS_MISO") (class "Default")
      (node (ref "IC32") (pin "7") (pinfunction "COM2_7") (pintype "passive"))
      (node (ref "IC33") (pin "2") (pinfunction "Q_2") (pintype "passive"))
    )
    (net (code "8") (name "/FLASH_AS_MOSI") (class "Default")
      (node (ref "IC32") (pin "4") (pinfunction "COM1_4") (pintype "passive"))
      (node (ref "IC33") (pin "5") (pinfunction "D_5") (pintype "passive"))
    )
    (net (code "9") (name "/FLASH_AS_SCLK") (class "Default")
      (node (ref "IC32") (pin "9") (pinfunction "COM3_9") (pintype "passive"))
      (node (ref "IC33") (pin "6") (pinfunction "C_6") (pintype "passive"))
      (node (ref "R187") (pin "1") (pinfunction "1_1") (pintype "passive"))
    )
    (net (code "10") (name "/FLASH_AS_SS") (class "Default")
      (node (ref "IC32") (pin "12") (pinfunction "COM4_12") (pintype "passive"))
      (node (ref "IC33") (pin "1") (pinfunction "S_1") (pintype "passive"))
      (node (ref "R188") (pin "2") (pinfunction "2_2") (pintype "passive"))
    )
    (net (code "11") (name "/FPGA_AS_ASDO") (class "Default")
      (node (ref "IC32") (pin "3") (pinfunction "NO1_3") (pintype "passive"))
    )
    (net (code "12") (name "/FPGA_AS_DATA0") (class "Default")
      (node (ref "R186") (pin "2") (pinfunction "2_2") (pintype "passive"))
    )
    (net (code "13") (name "/FPGA_AS_DCLK") (class "Default")
      (node (ref "IC31") (pin "K2") (pinfunction "DCLK_K2") (pintype "bidirectional"))
      (node (ref "IC32") (pin "10") (pinfunction "NO3_10") (pintype "passive"))
    )
    (net (code "14") (name "/FPGA_AS_NCSO") (class "Default")
      (node (ref "IC32") (pin "13") (pinfunction "NO4_13") (pintype "passive"))
    )
    (net (code "15") (name "/FPGA_CONF_DONE") (class "Default")
      (node (ref "IC31") (pin "M18") (pinfunction "CONF_DONE_M18") (pintype "bidirectional"))
    )
    (net (code "16") (name "/FPGA_GPIO0") (class "Default")
      (node (ref "J18") (pin "3") (pinfunction "3_3") (pintype "passive"))
    )
    (net (code "17") (name "/FPGA_GPIO1") (class "Default")
      (node (ref "J18") (pin "4") (pinfunction "4_4") (pintype "passive"))
    )
    (net (code "18") (name "/FPGA_GPIO2") (class "Default")
      (node (ref "J18") (pin "5") (pinfunction "5_5") (pintype "passive"))
    )
    (net (code "19") (name "/FPGA_GPIO3") (class "Default")
      (node (ref "J18") (pin "6") (pinfunction "6_6") (pintype "passive"))
    )
    (net (code "20") (name "/FPGA_GPIO4") (class "Default")
      (node (ref "J18") (pin "7") (pinfunction "7_7") (pintype "passive"))
    )
    (net (code "21") (name "/FPGA_GPIO5") (class "Default")
      (node (ref "J18") (pin "8") (pinfunction "8_8") (pintype "passive"))
    )
    (net (code "22") (name "/FPGA_GPIO6") (class "Default")
      (node (ref "J18") (pin "9") (pinfunction "9_9") (pintype "passive"))
    )
    (net (code "23") (name "/FPGA_GPIO7") (class "Default")
      (node (ref "J18") (pin "10") (pinfunction "10_10") (pintype "passive"))
    )
    (net (code "24") (name "/FPGA_JTAG_TCK") (class "Default")
      (node (ref "IC31") (pin "L2") (pinfunction "TCK_L2") (pintype "input"))
      (node (ref "J17") (pin "1") (pinfunction "1_1") (pintype "passive"))
      (node (ref "R180") (pin "1") (pinfunction "1_1") (pintype "passive"))
    )
    (net (code "25") (name "/FPGA_JTAG_TDI") (class "Default")
      (node (ref "IC31") (pin "L5") (pinfunction "TDI_L5") (pintype "input"))
      (node (ref "J17") (pin "9") (pinfunction "9_9") (pintype "passive"))
      (node (ref "R177") (pin "1") (pinfunction "1_1") (pintype "passive"))
    )
    (net (code "26") (name "/FPGA_JTAG_TDO") (class "Default")
      (node (ref "IC31") (pin "L4") (pinfunction "TDO_L4") (pintype "output"))
      (node (ref "J17") (pin "3") (pinfunction "3_3") (pintype "passive"))
    )
    (net (code "27") (name "/FPGA_JTAG_TMS") (class "Default")
      (node (ref "IC31") (pin "L1") (pinfunction "TMS_L1") (pintype "input"))
      (node (ref "J17") (pin "5") (pinfunction "5_5") (pintype "passive"))
      (node (ref "R176") (pin "1") (pinfunction "1_1") (pintype "passive"))
    )
    (net (code "28") (name "/FPGA_NCONFIG") (class "Default")
      (node (ref "IC31") (pin "K5") (pinfunction "nCONFIG_K5") (pintype "input"))
    )
    (net (code "29") (name "/FPGA_NSTATUS") (class "Default")
      (node (ref "IC31") (pin "K6") (pinfunction "nSTATUS_K6") (pintype "bidirectional"))
    )
    (net (code "30") (name "/LM75_OS") (class "Default")
      (node (ref "R182") (pin "1") (pinfunction "1_1") (pintype "passive"))
    )
    (net (code "31") (name "/LMK_CLK") (class "Default")
      (node (ref "IC31") (pin "B12") (pinfunction "CLK9,_DIFFCLK_5p_B12") (pintype "input"))
    )
    (net (code "32") (name "/LMS_MCLK1") (class "Default")
      (node (ref "IC31") (pin "G21") (pinfunction "CLK4,_DIFFCLK_2p_G21") (pintype "input"))
    )
    (net (code "33") (name "/LMS_MCLK2") (class "Default")
      (node (ref "IC31") (pin "B11") (pinfunction "CLK11,_DIFFCLK_4p_B11") (pintype "input"))
    )
    (net (code "34") (name "/MSEL0") (class "Default")
      (node (ref "IC31") (pin "M17") (pinfunction "MSEL0_M17") (pintype "input"))
      (node (ref "R168") (pin "1") (pinfunction "1_1") (pintype "passive"))
      (node (ref "R169") (pin "2") (pinfunction "2_2") (pintype "passive"))
    )
    (net (code "35") (name "/MSEL1") (class "Default")
      (node (ref "IC31") (pin "L18") (pinfunction "MSEL1_L18") (pintype "input"))
      (node (ref "R170") (pin "1") (pinfunction "1_1") (pintype "passive"))
      (node (ref "R171") (pin "2") (pinfunction "2_2") (pintype "passive"))
    )
    (net (code "36") (name "/MSEL2") (class "Default")
      (node (ref "IC31") (pin "L17") (pinfunction "MSEL2_L17") (pintype "input"))
      (node (ref "R174") (pin "1") (pinfunction "1_1") (pintype "passive"))
      (node (ref "R175") (pin "2") (pinfunction "2_2") (pintype "passive"))
    )
    (net (code "37") (name "/MSEL3") (class "Default")
      (node (ref "IC31") (pin "K20") (pinfunction "MSEL3_K20") (pintype "input"))
      (node (ref "R178") (pin "1") (pinfunction "1_1") (pintype "passive"))
      (node (ref "R179") (pin "2") (pinfunction "2_2") (pintype "passive"))
    )
    (net (code "38") (name "/SI_CLK0") (class "Default")
      (node (ref "IC31") (pin "T2") (pinfunction "CLK2,_DIFFCLK_1p_T2") (pintype "input"))
    )
    (net (code "39") (name "/SI_CLK1") (class "Default")
      (node (ref "IC31") (pin "AA12") (pinfunction "CLK13,_DIFFCLK_7p_AA12") (pintype "input"))
    )
    (net (code "40") (name "/SI_CLK2") (class "Default")
      (node (ref "IC31") (pin "T21") (pinfunction "CLK6,_DIFFCLK_3p_T21") (pintype "input"))
    )
    (net (code "41") (name "/SI_CLK3") (class "Default")
      (node (ref "IC31") (pin "T22") (pinfunction "CLK7,_DIFFCLK_3n_T22") (pintype "input"))
    )
    (net (code "42") (name "/SI_CLK5") (class "Default")
      (node (ref "IC31") (pin "G1") (pinfunction "CLK1,_DIFFCLK_0n_G1") (pintype "input"))
    )
    (net (code "43") (name "/SI_CLK6") (class "Default")
      (node (ref "IC31") (pin "AA11") (pinfunction "CLK15,_DIFFCLK_6p_AA11") (pintype "input"))
    )
    (net (code "44") (name "/SI_CLK7") (class "Default")
      (node (ref "IC31") (pin "AB11") (pinfunction "CLK14,_DIFFCLK_6n_AB11") (pintype "input"))
    )
    (net (code "45") (name "GND") (class "Default")
      (node (ref "C294") (pin "1") (pinfunction "1_1") (pintype "passive"))
      (node (ref "C295") (pin "1") (pinfunction "1_1") (pintype "passive"))
      (node (ref "C296") (pin "1") (pinfunction "1_1") (pintype "passive"))
      (node (ref "C297") (pin "2") (pinfunction "2_2") (pintype "passive"))
      (node (ref "C298") (pin "2") (pinfunction "2_2") (pintype "passive"))
      (node (ref "C299") (pin "1") (pinfunction "1_1") (pintype "passive"))
      (node (ref "C300") (pin "1") (pinfunction "1_1") (pintype "passive"))
      (node (ref "C301") (pin "1") (pinfunction "1_1") (pintype "passive"))
      (node (ref "C302") (pin "2") (pinfunction "2_2") (pintype "passive"))
      (node (ref "C303") (pin "2") (pinfunction "2_2") (pintype "passive"))
      (node (ref "C304") (pin "2") (pinfunction "2_2") (pintype "passive"))
      (node (ref "C305") (pin "1") (pinfunction "1_1") (pintype "passive"))
      (node (ref "C306") (pin "1") (pinfunction "1_1") (pintype "passive"))
      (node (ref "C307") (pin "1") (pinfunction "1_1") (pintype "passive"))
      (node (ref "C308") (pin "1") (pinfunction "1_1") (pintype "passive"))
      (node (ref "C309") (pin "1") (pinfunction "1_1") (pintype "passive"))
      (node (ref "C310") (pin "2") (pinfunction "2_2") (pintype "passive"))
      (node (ref "C311") (pin "1") (pinfunction "1_1") (pintype "passive"))
      (node (ref "C312") (pin "1") (pinfunction "1_1") (pintype "passive"))
      (node (ref "C313") (pin "1") (pinfunction "1_1") (pintype "passive"))
      (node (ref "C314") (pin "1") (pinfunction "1_1") (pintype "passive"))
      (node (ref "C315") (pin "2") (pinfunction "2_2") (pintype "passive"))
      (node (ref "C316") (pin "1") (pinfunction "1_1") (pintype "passive"))
      (node (ref "C317") (pin "1") (pinfunction "1_1") (pintype "passive"))
      (node (ref "C318") (pin "1") (pinfunction "1_1") (pintype "passive"))
      (node (ref "C319") (pin "1") (pinfunction "1_1") (pintype "passive"))
      (node (ref "C320") (pin "2") (pinfunction "2_2") (pintype "passive"))
      (node (ref "C321") (pin "1") (pinfunction "1_1") (pintype "passive"))
      (node (ref "C322") (pin "1") (pinfunction "1_1") (pintype "passive"))
      (node (ref "C323") (pin "1") (pinfunction "1_1") (pintype "passive"))
      (node (ref "C324") (pin "1") (pinfunction "1_1") (pintype "passive"))
      (node (ref "C325") (pin "2") (pinfunction "2_2") (pintype "passive"))
      (node (ref "C326") (pin "2") (pinfunction "2_2") (pintype "passive"))
      (node (ref "C327") (pin "2") (pinfunction "2_2") (pintype "passive"))
      (node (ref "C328") (pin "2") (pinfunction "2_2") (pintype "passive"))
      (node (ref "C329") (pin "2") (pinfunction "2_2") (pintype "passive"))
      (node (ref "C330") (pin "2") (pinfunction "2_2") (pintype "passive"))
      (node (ref "C331") (pin "2") (pinfunction "2_2") (pintype "passive"))
      (node (ref "C332") (pin "2") (pinfunction "2_2") (pintype "passive"))
      (node (ref "C333") (pin "2") (pinfunction "2_2") (pintype "passive"))
      (node (ref "C334") (pin "2") (pinfunction "2_2") (pintype "passive"))
      (node (ref "C335") (pin "2") (pinfunction "2_2") (pintype "passive"))
      (node (ref "C336") (pin "2") (pinfunction "2_2") (pintype "passive"))
      (node (ref "C337") (pin "2") (pinfunction "2_2") (pintype "passive"))
      (node (ref "C338") (pin "2") (pinfunction "2_2") (pintype "passive"))
      (node (ref "C339") (pin "2") (pinfunction "2_2") (pintype "passive"))
      (node (ref "C340") (pin "2") (pinfunction "2_2") (pintype "passive"))
      (node (ref "C341") (pin "2") (pinfunction "2_2") (pintype "passive"))
      (node (ref "C342") (pin "2") (pinfunction "2_2") (pintype "passive"))
      (node (ref "C343") (pin "2") (pinfunction "2_2") (pintype "passive"))
      (node (ref "C344") (pin "2") (pinfunction "2_2") (pintype "passive"))
      (node (ref "C345") (pin "2") (pinfunction "2_2") (pintype "passive"))
      (node (ref "C346") (pin "2") (pinfunction "2_2") (pintype "passive"))
      (node (ref "C347") (pin "2") (pinfunction "2_2") (pintype "passive"))
      (node (ref "C348") (pin "2") (pinfunction "2_2") (pintype "passive"))
      (node (ref "C349") (pin "2") (pinfunction "2_2") (pintype "passive"))
      (node (ref "C350") (pin "2") (pinfunction "2_2") (pintype "passive"))
      (node (ref "C351") (pin "2") (pinfunction "2_2") (pintype "passive"))
      (node (ref "C352") (pin "2") (pinfunction "2_2") (pintype "passive"))
      (node (ref "C353") (pin "2") (pinfunction "2_2") (pintype "passive"))
      (node (ref "C354") (pin "2") (pinfunction "2_2") (pintype "passive"))
      (node (ref "C355") (pin "2") (pinfunction "2_2") (pintype "passive"))
      (node (ref "C356") (pin "2") (pinfunction "2_2") (pintype "passive"))
      (node (ref "C357") (pin "2") (pinfunction "2_2") (pintype "passive"))
      (node (ref "C358") (pin "2") (pinfunction "2_2") (pintype "passive"))
      (node (ref "C359") (pin "2") (pinfunction "2_2") (pintype "passive"))
      (node (ref "C360") (pin "2") (pinfunction "2_2") (pintype "passive"))
      (node (ref "C361") (pin "2") (pinfunction "2_2") (pintype "passive"))
      (node (ref "C362") (pin "2") (pinfunction "2_2") (pintype "passive"))
      (node (ref "C363") (pin "2") (pinfunction "2_2") (pintype "passive"))
      (node (ref "C364") (pin "2") (pinfunction "2_2") (pintype "passive"))
      (node (ref "C365") (pin "2") (pinfunction "2_2") (pintype "passive"))
      (node (ref "C366") (pin "2") (pinfunction "2_2") (pintype "passive"))
      (node (ref "C367") (pin "2") (pinfunction "2_2") (pintype "passive"))
      (node (ref "C368") (pin "2") (pinfunction "2_2") (pintype "passive"))
      (node (ref "C369") (pin "2") (pinfunction "2_2") (pintype "passive"))
      (node (ref "C370") (pin "2") (pinfunction "2_2") (pintype "passive"))
      (node (ref "C371") (pin "2") (pinfunction "2_2") (pintype "passive"))
      (node (ref "C372") (pin "2") (pinfunction "2_2") (pintype "passive"))
      (node (ref "C373") (pin "2") (pinfunction "2_2") (pintype "passive"))
      (node (ref "C374") (pin "2") (pinfunction "2_2") (pintype "passive"))
      (node (ref "C375") (pin "2") (pinfunction "2_2") (pintype "passive"))
      (node (ref "C376") (pin "2") (pinfunction "2_2") (pintype "passive"))
      (node (ref "C377") (pin "2") (pinfunction "2_2") (pintype "passive"))
      (node (ref "C378") (pin "2") (pinfunction "2_2") (pintype "passive"))
      (node (ref "C379") (pin "2") (pinfunction "2_2") (pintype "passive"))
      (node (ref "C380") (pin "2") (pinfunction "2_2") (pintype "passive"))
      (node (ref "C381") (pin "2") (pinfunction "2_2") (pintype "passive"))
      (node (ref "C382") (pin "2") (pinfunction "2_2") (pintype "passive"))
      (node (ref "C383") (pin "2") (pinfunction "2_2") (pintype "passive"))
      (node (ref "C384") (pin "2") (pinfunction "2_2") (pintype "passive"))
      (node (ref "C385") (pin "2") (pinfunction "2_2") (pintype "passive"))
      (node (ref "C386") (pin "2") (pinfunction "2_2") (pintype "passive"))
      (node (ref "C387") (pin "2") (pinfunction "2_2") (pintype "passive"))
      (node (ref "C388") (pin "2") (pinfunction "2_2") (pintype "passive"))
      (node (ref "C389") (pin "2") (pinfunction "2_2") (pintype "passive"))
      (node (ref "C390") (pin "2") (pinfunction "2_2") (pintype "passive"))
      (node (ref "C391") (pin "2") (pinfunction "2_2") (pintype "passive"))
      (node (ref "C392") (pin "2") (pinfunction "2_2") (pintype "passive"))
      (node (ref "C393") (pin "2") (pinfunction "2_2") (pintype "passive"))
      (node (ref "C394") (pin "2") (pinfunction "2_2") (pintype "passive"))
      (node (ref "C395") (pin "2") (pinfunction "2_2") (pintype "passive"))
      (node (ref "C396") (pin "2") (pinfunction "2_2") (pintype "passive"))
      (node (ref "C397") (pin "2") (pinfunction "2_2") (pintype "passive"))
      (node (ref "C398") (pin "2") (pinfunction "2_2") (pintype "passive"))
      (node (ref "C399") (pin "2") (pinfunction "2_2") (pintype "passive"))
      (node (ref "IC31") (pin "A1") (pinfunction "GND_A1") (pintype "power_in"))
      (node (ref "IC31") (pin "A11") (pinfunction "CLK10,_DIFFCLK_4n_A11") (pintype "input"))
      (node (ref "IC31") (pin "A12") (pinfunction "CLK8,_DIFFCLK_5n_A12") (pintype "input"))
      (node (ref "IC31") (pin "A22") (pinfunction "GND_A22") (pintype "power_in"))
      (node (ref "IC31") (pin "AA2") (pinfunction "GND_AA2") (pintype "power_in"))
      (node (ref "IC31") (pin "AA22") (pinfunction "GND_AA22") (pintype "power_in"))
      (node (ref "IC31") (pin "AB1") (pinfunction "GND_AB1") (pintype "power_in"))
      (node (ref "IC31") (pin "AB12") (pinfunction "CLK12,_DIFFCLK_7n_AB12") (pintype "input"))
      (node (ref "IC31") (pin "AB22") (pinfunction "GND_AB22") (pintype "power_in"))
      (node (ref "IC31") (pin "AB6") (pinfunction "GND_AB6") (pintype "power_in"))
      (node (ref "IC31") (pin "C11") (pinfunction "GND_C11") (pintype "power_in"))
      (node (ref "IC31") (pin "C12") (pinfunction "GND_C12") (pintype "power_in"))
      (node (ref "IC31") (pin "C14") (pinfunction "GND_C14") (pintype "power_in"))
      (node (ref "IC31") (pin "C16") (pinfunction "GND_C16") (pintype "power_in"))
      (node (ref "IC31") (pin "C18") (pinfunction "GND_C18") (pintype "power_in"))
      (node (ref "IC31") (pin "C5") (pinfunction "GND_C5") (pintype "power_in"))
      (node (ref "IC31") (pin "C9") (pinfunction "GND_C9") (pintype "power_in"))
      (node (ref "IC31") (pin "D3") (pinfunction "GND_D3") (pintype "power_in"))
      (node (ref "IC31") (pin "D8") (pinfunction "GND_D8") (pintype "power_in"))
      (node (ref "IC31") (pin "E18") (pinfunction "GNDA2_E18") (pintype "power_in"))
      (node (ref "IC31") (pin "E20") (pinfunction "GND_E20") (pintype "power_in"))
      (node (ref "IC31") (pin "F12") (pinfunction "GND_F12") (pintype "power_in"))
      (node (ref "IC31") (pin "F3") (pinfunction "GND_F3") (pintype "power_in"))
      (node (ref "IC31") (pin "F5") (pinfunction "GNDA3_F5") (pintype "power_in"))
      (node (ref "IC31") (pin "G2") (pinfunction "GND_G2") (pintype "power_in"))
      (node (ref "IC31") (pin "G20") (pinfunction "GND_G20") (pintype "power_in"))
      (node (ref "IC31") (pin "G22") (pinfunction "CLK5,_DIFFCLK_2n_G22") (pintype "input"))
      (node (ref "IC31") (pin "H12") (pinfunction "GND_H12") (pintype "power_in"))
      (node (ref "IC31") (pin "H13") (pinfunction "GND_H13") (pintype "power_in"))
      (node (ref "IC31") (pin "H3") (pinfunction "GND_H3") (pintype "power_in"))
      (node (ref "IC31") (pin "J15") (pinfunction "GND_J15") (pintype "power_in"))
      (node (ref "IC31") (pin "J19") (pinfunction "GND_J19") (pintype "power_in"))
      (node (ref "IC31") (pin "J9") (pinfunction "GND_J9") (pintype "power_in"))
      (node (ref "IC31") (pin "K10") (pinfunction "GND_K10") (pintype "power_in"))
      (node (ref "IC31") (pin "K11") (pinfunction "GND_K11") (pintype "power_in"))
      (node (ref "IC31") (pin "K12") (pinfunction "GND_K12") (pintype "power_in"))
      (node (ref "IC31") (pin "K13") (pinfunction "GND_K13") (pintype "power_in"))
      (node (ref "IC31") (pin "K16") (pinfunction "GND_K16") (pintype "power_in"))
      (node (ref "IC31") (pin "K3") (pinfunction "GND_K3") (pintype "power_in"))
      (node (ref "IC31") (pin "L10") (pinfunction "GND_L10") (pintype "power_in"))
      (node (ref "IC31") (pin "L11") (pinfunction "GND_L11") (pintype "power_in"))
      (node (ref "IC31") (pin "L12") (pinfunction "GND_L12") (pintype "power_in"))
      (node (ref "IC31") (pin "L13") (pinfunction "GND_L13") (pintype "power_in"))
      (node (ref "IC31") (pin "L15") (pinfunction "GND_L15") (pintype "power_in"))
      (node (ref "IC31") (pin "L20") (pinfunction "GND_L20") (pintype "power_in"))
      (node (ref "IC31") (pin "L3") (pinfunction "nCE_L3") (pintype "input"))
      (node (ref "IC31") (pin "M10") (pinfunction "GND_M10") (pintype "power_in"))
      (node (ref "IC31") (pin "M11") (pinfunction "GND_M11") (pintype "power_in"))
      (node (ref "IC31") (pin "M12") (pinfunction "GND_M12") (pintype "power_in"))
      (node (ref "IC31") (pin "M13") (pinfunction "GND_M13") (pintype "power_in"))
      (node (ref "IC31") (pin "N10") (pinfunction "GND_N10") (pintype "power_in"))
      (node (ref "IC31") (pin "N11") (pinfunction "GND_N11") (pintype "power_in"))
      (node (ref "IC31") (pin "N12") (pinfunction "GND_N12") (pintype "power_in"))
      (node (ref "IC31") (pin "N13") (pinfunction "GND_N13") (pintype "power_in"))
      (node (ref "IC31") (pin "N15") (pinfunction "GND_N15") (pintype "power_in"))
      (node (ref "IC31") (pin "N3") (pinfunction "GND_N3") (pintype "power_in"))
      (node (ref "IC31") (pin "P19") (pinfunction "GND_P19") (pintype "power_in"))
      (node (ref "IC31") (pin "P8") (pinfunction "GND_P8") (pintype "power_in"))
      (node (ref "IC31") (pin "R11") (pinfunction "GND_R11") (pintype "power_in"))
      (node (ref "IC31") (pin "R13") (pinfunction "GND_R13") (pintype "power_in"))
      (node (ref "IC31") (pin "R3") (pinfunction "GND_R3") (pintype "power_in"))
      (node (ref "IC31") (pin "R9") (pinfunction "GND_R9") (pintype "power_in"))
      (node (ref "IC31") (pin "T1") (pinfunction "CLK3,_DIFFCLK_1n_T1") (pintype "input"))
      (node (ref "IC31") (pin "T20") (pinfunction "GND_T20") (pintype "power_in"))
      (node (ref "IC31") (pin "U3") (pinfunction "GND_U3") (pintype "power_in"))
      (node (ref "IC31") (pin "U5") (pinfunction "GNDA1_U5") (pintype "power_in"))
      (node (ref "IC31") (pin "V18") (pinfunction "GNDA4_V18") (pintype "power_in"))
      (node (ref "IC31") (pin "V20") (pinfunction "GND_V20") (pintype "power_in"))
      (node (ref "IC31") (pin "W3") (pinfunction "GND_W3") (pintype "power_in"))
      (node (ref "IC31") (pin "Y11") (pinfunction "GND_Y11") (pintype "power_in"))
      (node (ref "IC31") (pin "Y12") (pinfunction "GND_Y12") (pintype "power_in"))
      (node (ref "IC31") (pin "Y15") (pinfunction "GND_Y15") (pintype "power_in"))
      (node (ref "IC31") (pin "Y16") (pinfunction "GND_Y16") (pintype "power_in"))
      (node (ref "IC31") (pin "Y18") (pinfunction "GND_Y18") (pintype "power_in"))
      (node (ref "IC31") (pin "Y20") (pinfunction "GND_Y20") (pintype "power_in"))
      (node (ref "IC31") (pin "Y5") (pinfunction "GND_Y5") (pintype "power_in"))
      (node (ref "IC31") (pin "Y9") (pinfunction "GND_Y9") (pintype "power_in"))
      (node (ref "IC32") (pin "15") (pinfunction "~{EN}_15") (pintype "passive"))
      (node (ref "IC32") (pin "8") (pinfunction "GND_8") (pintype "passive"))
      (node (ref "IC33") (pin "4") (pinfunction "GND_4") (pintype "passive"))
      (node (ref "J17") (pin "10") (pinfunction "10_10") (pintype "passive"))
      (node (ref "J17") (pin "2") (pinfunction "2_2") (pintype "passive"))
      (node (ref "J18") (pin "1") (pinfunction "1_1") (pintype "passive"))
      (node (ref "R168") (pin "2") (pinfunction "2_2") (pintype "passive"))
      (node (ref "R170") (pin "2") (pinfunction "2_2") (pintype "passive"))
      (node (ref "R174") (pin "2") (pinfunction "2_2") (pintype "passive"))
      (node (ref "R178") (pin "2") (pinfunction "2_2") (pintype "passive"))
      (node (ref "R180") (pin "2") (pinfunction "2_2") (pintype "passive"))
      (node (ref "R185") (pin "2") (pinfunction "2_2") (pintype "passive"))
      (node (ref "R187") (pin "2") (pinfunction "2_2") (pintype "passive"))
      (node (ref "VT1") (pin "S") (pinfunction "S_S") (pintype "passive"))
    )
    (net (code "46") (name "Net-(IC32-IN)") (class "Default")
      (node (ref "IC32") (pin "1") (pinfunction "IN_1") (pintype "passive"))
      (node (ref "R181") (pin "1") (pinfunction "1_1") (pintype "passive"))
      (node (ref "R183") (pin "2") (pinfunction "2_2") (pintype "passive"))
      (node (ref "R184") (pin "1") (pinfunction "1_1") (pintype "passive"))
    )
    (net (code "47") (name "Net-(IC32-NO2)") (class "Default")
      (node (ref "IC32") (pin "6") (pinfunction "NO2_6") (pintype "passive"))
      (node (ref "R186") (pin "1") (pinfunction "1_1") (pintype "passive"))
    )
    (net (code "48") (name "Net-(IC33-HOLD)") (class "Default")
      (node (ref "IC33") (pin "7") (pinfunction "HOLD_7") (pintype "passive"))
      (node (ref "R189") (pin "2") (pinfunction "2_2") (pintype "passive"))
    )
    (net (code "49") (name "Net-(IC33-W)") (class "Default")
      (node (ref "IC33") (pin "3") (pinfunction "W_3") (pintype "passive"))
      (node (ref "R190") (pin "2") (pinfunction "2_2") (pintype "passive"))
    )
    (net (code "50") (name "Net-(J18-Pad2)") (class "Default")
      (node (ref "J18") (pin "2") (pinfunction "2_2") (pintype "passive"))
      (node (ref "R172") (pin "2") (pinfunction "2_2") (pintype "passive"))
      (node (ref "R173") (pin "2") (pinfunction "2_2") (pintype "passive"))
    )
    (net (code "51") (name "Net-(J19-Pad1)") (class "Default")
      (node (ref "J19") (pin "1") (pinfunction "1_1") (pintype "passive"))
      (node (ref "J20") (pin "1") (pinfunction "1_1") (pintype "passive"))
      (node (ref "VT1") (pin "D") (pinfunction "D_D") (pintype "passive"))
    )
    (net (code "52") (name "VCC1P2") (class "Default")
      (node (ref "C294") (pin "2") (pinfunction "2_2") (pintype "passive"))
      (node (ref "C295") (pin "2") (pinfunction "2_2") (pintype "passive"))
      (node (ref "C296") (pin "2") (pinfunction "2_2") (pintype "passive"))
      (node (ref "C297") (pin "1") (pinfunction "1_1") (pintype "passive"))
      (node (ref "C298") (pin "1") (pinfunction "1_1") (pintype "passive"))
      (node (ref "C368") (pin "1") (pinfunction "1_1") (pintype "passive"))
      (node (ref "C369") (pin "1") (pinfunction "1_1") (pintype "passive"))
      (node (ref "C370") (pin "1") (pinfunction "1_1") (pintype "passive"))
      (node (ref "C371") (pin "1") (pinfunction "1_1") (pintype "passive"))
      (node (ref "C372") (pin "1") (pinfunction "1_1") (pintype "passive"))
      (node (ref "C373") (pin "1") (pinfunction "1_1") (pintype "passive"))
      (node (ref "C374") (pin "1") (pinfunction "1_1") (pintype "passive"))
      (node (ref "C375") (pin "1") (pinfunction "1_1") (pintype "passive"))
      (node (ref "C376") (pin "1") (pinfunction "1_1") (pintype "passive"))
      (node (ref "C377") (pin "1") (pinfunction "1_1") (pintype "passive"))
      (node (ref "C378") (pin "1") (pinfunction "1_1") (pintype "passive"))
      (node (ref "C379") (pin "1") (pinfunction "1_1") (pintype "passive"))
      (node (ref "C380") (pin "1") (pinfunction "1_1") (pintype "passive"))
      (node (ref "C381") (pin "1") (pinfunction "1_1") (pintype "passive"))
      (node (ref "C386") (pin "1") (pinfunction "1_1") (pintype "passive"))
      (node (ref "C387") (pin "1") (pinfunction "1_1") (pintype "passive"))
      (node (ref "C388") (pin "1") (pinfunction "1_1") (pintype "passive"))
      (node (ref "C389") (pin "1") (pinfunction "1_1") (pintype "passive"))
      (node (ref "C390") (pin "1") (pinfunction "1_1") (pintype "passive"))
      (node (ref "C391") (pin "1") (pinfunction "1_1") (pintype "passive"))
      (node (ref "C392") (pin "1") (pinfunction "1_1") (pintype "passive"))
      (node (ref "C393") (pin "1") (pinfunction "1_1") (pintype "passive"))
      (node (ref "C394") (pin "1") (pinfunction "1_1") (pintype "passive"))
      (node (ref "C395") (pin "1") (pinfunction "1_1") (pintype "passive"))
      (node (ref "C396") (pin "1") (pinfunction "1_1") (pintype "passive"))
      (node (ref "C397") (pin "1") (pinfunction "1_1") (pintype "passive"))
      (node (ref "C398") (pin "1") (pinfunction "1_1") (pintype "passive"))
      (node (ref "C399") (pin "1") (pinfunction "1_1") (pintype "passive"))
      (node (ref "FR60") (pin "1") (pinfunction "1_1") (pintype "passive"))
      (node (ref "IC31") (pin "G12") (pinfunction "VCCINT_G12") (pintype "power_in"))
      (node (ref "IC31") (pin "H9") (pinfunction "VCCINT_H9") (pintype "power_in"))
      (node (ref "IC31") (pin "J10") (pinfunction "VCCINT_J10") (pintype "power_in"))
      (node (ref "IC31") (pin "J11") (pinfunction "VCCINT_J11") (pintype "power_in"))
      (node (ref "IC31") (pin "J12") (pinfunction "VCCINT_J12") (pintype "power_in"))
      (node (ref "IC31") (pin "J13") (pinfunction "VCCINT_J13") (pintype "power_in"))
      (node (ref "IC31") (pin "J14") (pinfunction "VCCINT_J14") (pintype "power_in"))
      (node (ref "IC31") (pin "J16") (pinfunction "VCCINT_J16") (pintype "power_in"))
      (node (ref "IC31") (pin "K14") (pinfunction "VCCINT_K14") (pintype "power_in"))
      (node (ref "IC31") (pin "K15") (pinfunction "VCCINT_K15") (pintype "power_in"))
      (node (ref "IC31") (pin "K9") (pinfunction "VCCINT_K9") (pintype "power_in"))
      (node (ref "IC31") (pin "L14") (pinfunction "VCCINT_L14") (pintype "power_in"))
      (node (ref "IC31") (pin "L16") (pinfunction "VCCINT_L16") (pintype "power_in"))
      (node (ref "IC31") (pin "L9") (pinfunction "VCCINT_L9") (pintype "power_in"))
      (node (ref "IC31") (pin "M14") (pinfunction "VCCINT_M14") (pintype "power_in"))
      (node (ref "IC31") (pin "M15") (pinfunction "VCCINT_M15") (pintype "power_in"))
      (node (ref "IC31") (pin "M9") (pinfunction "VCCINT_M9") (pintype "power_in"))
      (node (ref "IC31") (pin "N14") (pinfunction "VCCINT_N14") (pintype "power_in"))
      (node (ref "IC31") (pin "N9") (pinfunction "VCCINT_N9") (pintype "power_in"))
      (node (ref "IC31") (pin "P10") (pinfunction "VCCINT_P10") (pintype "power_in"))
      (node (ref "IC31") (pin "P11") (pinfunction "VCCINT_P11") (pintype "power_in"))
      (node (ref "IC31") (pin "P12") (pinfunction "VCCINT_P12") (pintype "power_in"))
      (node (ref "IC31") (pin "P13") (pinfunction "VCCINT_P13") (pintype "power_in"))
      (node (ref "IC31") (pin "P14") (pinfunction "VCCINT_P14") (pintype "power_in"))
      (node (ref "IC31") (pin "P9") (pinfunction "VCCINT_P9") (pintype "power_in"))
      (node (ref "IC31") (pin "R10") (pinfunction "VCCINT_R10") (pintype "power_in"))
      (node (ref "IC31") (pin "R12") (pinfunction "VCCINT_R12") (pintype "power_in"))
      (node (ref "IC31") (pin "R8") (pinfunction "VCCINT_R8") (pintype "power_in"))
    )
    (net (code "53") (name "VCC1P2D") (class "Default")
      (node (ref "C299") (pin "2") (pinfunction "2_2") (pintype "passive"))
      (node (ref "C300") (pin "2") (pinfunction "2_2") (pintype "passive"))
      (node (ref "C301") (pin "2") (pinfunction "2_2") (pintype "passive"))
      (node (ref "C302") (pin "1") (pinfunction "1_1") (pintype "passive"))
      (node (ref "C303") (pin "1") (pinfunction "1_1") (pintype "passive"))
      (node (ref "C382") (pin "1") (pinfunction "1_1") (pintype "passive"))
      (node (ref "C383") (pin "1") (pinfunction "1_1") (pintype "passive"))
      (node (ref "C384") (pin "1") (pinfunction "1_1") (pintype "passive"))
      (node (ref "C385") (pin "1") (pinfunction "1_1") (pintype "passive"))
      (node (ref "FR60") (pin "2") (pinfunction "2_2") (pintype "passive"))
      (node (ref "IC31") (pin "E17") (pinfunction "VCCD_PLL2_E17") (pintype "power_in"))
      (node (ref "IC31") (pin "F6") (pinfunction "VCCD_PLL3_F6") (pintype "power_in"))
      (node (ref "IC31") (pin "U6") (pinfunction "VCCD_PLL1_U6") (pintype "power_in"))
      (node (ref "IC31") (pin "V17") (pinfunction "VCCD_PLL4_V17") (pintype "power_in"))
    )
    (net (code "54") (name "VCC1P8") (class "Default")
      (node (ref "C305") (pin "2") (pinfunction "2_2") (pintype "passive"))
      (node (ref "C306") (pin "2") (pinfunction "2_2") (pintype "passive"))
      (node (ref "C307") (pin "2") (pinfunction "2_2") (pintype "passive"))
      (node (ref "C308") (pin "2") (pinfunction "2_2") (pintype "passive"))
      (node (ref "C309") (pin "2") (pinfunction "2_2") (pintype "passive"))
      (node (ref "C310") (pin "1") (pinfunction "1_1") (pintype "passive"))
      (node (ref "C350") (pin "1") (pinfunction "1_1") (pintype "passive"))
      (node (ref "C351") (pin "1") (pinfunction "1_1") (pintype "passive"))
      (node (ref "C352") (pin "1") (pinfunction "1_1") (pintype "passive"))
      (node (ref "C353") (pin "1") (pinfunction "1_1") (pintype "passive"))
      (node (ref "C354") (pin "1") (pinfunction "1_1") (pintype "passive"))
      (node (ref "C355") (pin "1") (pinfunction "1_1") (pintype "passive"))
      (node (ref "C356") (pin "1") (pinfunction "1_1") (pintype "passive"))
      (node (ref "C357") (pin "1") (pinfunction "1_1") (pintype "passive"))
      (node (ref "C358") (pin "1") (pinfunction "1_1") (pintype "passive"))
      (node (ref "C359") (pin "1") (pinfunction "1_1") (pintype "passive"))
      (node (ref "C360") (pin "1") (pinfunction "1_1") (pintype "passive"))
      (node (ref "C361") (pin "1") (pinfunction "1_1") (pintype "passive"))
      (node (ref "C362") (pin "1") (pinfunction "1_1") (pintype "passive"))
      (node (ref "C363") (pin "1") (pinfunction "1_1") (pintype "passive"))
      (node (ref "C364") (pin "1") (pinfunction "1_1") (pintype "passive"))
      (node (ref "C365") (pin "1") (pinfunction "1_1") (pintype "passive"))
      (node (ref "C366") (pin "1") (pinfunction "1_1") (pintype "passive"))
      (node (ref "C367") (pin "1") (pinfunction "1_1") (pintype "passive"))
      (node (ref "IC31") (pin "AA6") (pinfunction "VCCIO3_AA6") (pintype "power_in"))
      (node (ref "IC31") (pin "AB2") (pinfunction "VCCIO3_AB2") (pintype "power_in"))
      (node (ref "IC31") (pin "AB21") (pinfunction "VCCIO4_AB21") (pintype "power_in"))
      (node (ref "IC31") (pin "N4") (pinfunction "VCCIO2_N4") (pintype "power_in"))
      (node (ref "IC31") (pin "P18") (pinfunction "VCCIO5_P18") (pintype "power_in"))
      (node (ref "IC31") (pin "R4") (pinfunction "VCCIO2_R4") (pintype "power_in"))
      (node (ref "IC31") (pin "T19") (pinfunction "VCCIO5_T19") (pintype "power_in"))
      (node (ref "IC31") (pin "U4") (pinfunction "VCCIO2_U4") (pintype "power_in"))
      (node (ref "IC31") (pin "V19") (pinfunction "VCCIO5_V19") (pintype "power_in"))
      (node (ref "IC31") (pin "W11") (pinfunction "VCCIO3_W11") (pintype "power_in"))
      (node (ref "IC31") (pin "W12") (pinfunction "VCCIO4_W12") (pintype "power_in"))
      (node (ref "IC31") (pin "W16") (pinfunction "VCCIO4_W16") (pintype "power_in"))
      (node (ref "IC31") (pin "W18") (pinfunction "VCCIO4_W18") (pintype "power_in"))
      (node (ref "IC31") (pin "W4") (pinfunction "VCCIO2_W4") (pintype "power_in"))
      (node (ref "IC31") (pin "W5") (pinfunction "VCCIO3_W5") (pintype "power_in"))
      (node (ref "IC31") (pin "W9") (pinfunction "VCCIO3_W9") (pintype "power_in"))
      (node (ref "IC31") (pin "Y14") (pinfunction "VCCIO4_Y14") (pintype "power_in"))
      (node (ref "IC31") (pin "Y19") (pinfunction "VCCIO5_Y19") (pintype "power_in"))
    )
    (net (code "55") (name "VCC2P5") (class "Default")
      (node (ref "FR61") (pin "1") (pinfunction "1_1") (pintype "passive"))
    )
    (net (code "56") (name "VCC2P5A") (class "Default")
      (node (ref "C311") (pin "2") (pinfunction "2_2") (pintype "passive"))
      (node (ref "C312") (pin "2") (pinfunction "2_2") (pintype "passive"))
      (node (ref "C313") (pin "2") (pinfunction "2_2") (pintype "passive"))
      (node (ref "C314") (pin "2") (pinfunction "2_2") (pintype "passive"))
      (node (ref "C315") (pin "1") (pinfunction "1_1") (pintype "passive"))
      (node (ref "C328") (pin "1") (pinfunction "1_1") (pintype "passive"))
      (node (ref "C329") (pin "1") (pinfunction "1_1") (pintype "passive"))
      (node (ref "C330") (pin "1") (pinfunction "1_1") (pintype "passive"))
      (node (ref "C331") (pin "1") (pinfunction "1_1") (pintype "passive"))
      (node (ref "FR61") (pin "2") (pinfunction "2_2") (pintype "passive"))
      (node (ref "IC31") (pin "F18") (pinfunction "VCCA2_F18") (pintype "power_in"))
      (node (ref "IC31") (pin "G6") (pinfunction "VCCA3_G6") (pintype "power_in"))
      (node (ref "IC31") (pin "T6") (pinfunction "VCCA1_T6") (pintype "power_in"))
      (node (ref "IC31") (pin "U18") (pinfunction "VCCA4_U18") (pintype "power_in"))
      (node (ref "J17") (pin "4") (pinfunction "4_4") (pintype "passive"))
      (node (ref "R169") (pin "1") (pinfunction "1_1") (pintype "passive"))
      (node (ref "R171") (pin "1") (pinfunction "1_1") (pintype "passive"))
      (node (ref "R175") (pin "1") (pinfunction "1_1") (pintype "passive"))
      (node (ref "R176") (pin "2") (pinfunction "2_2") (pintype "passive"))
      (node (ref "R177") (pin "2") (pinfunction "2_2") (pintype "passive"))
      (node (ref "R179") (pin "1") (pinfunction "1_1") (pintype "passive"))
    )
    (net (code "57") (name "VCC3P3") (class "Default")
      (node (ref "C304") (pin "1") (pinfunction "1_1") (pintype "passive"))
      (node (ref "C321") (pin "2") (pinfunction "2_2") (pintype "passive"))
      (node (ref "C322") (pin "2") (pinfunction "2_2") (pintype "passive"))
      (node (ref "C323") (pin "2") (pinfunction "2_2") (pintype "passive"))
      (node (ref "C324") (pin "2") (pinfunction "2_2") (pintype "passive"))
      (node (ref "C325") (pin "1") (pinfunction "1_1") (pintype "passive"))
      (node (ref "C326") (pin "1") (pinfunction "1_1") (pintype "passive"))
      (node (ref "C327") (pin "1") (pinfunction "1_1") (pintype "passive"))
      (node (ref "C346") (pin "1") (pinfunction "1_1") (pintype "passive"))
      (node (ref "C347") (pin "1") (pinfunction "1_1") (pintype "passive"))
      (node (ref "C348") (pin "1") (pinfunction "1_1") (pintype "passive"))
      (node (ref "C349") (pin "1") (pinfunction "1_1") (pintype "passive"))
      (node (ref "IC31") (pin "D4") (pinfunction "VCCIO1_D4") (pintype "power_in"))
      (node (ref "IC31") (pin "F4") (pinfunction "VCCIO1_F4") (pintype "power_in"))
      (node (ref "IC31") (pin "H4") (pinfunction "VCCIO1_H4") (pintype "power_in"))
      (node (ref "IC31") (pin "K4") (pinfunction "VCCIO1_K4") (pintype "power_in"))
      (node (ref "IC32") (pin "16") (pinfunction "V+_16") (pintype "passive"))
      (node (ref "IC33") (pin "8") (pinfunction "VCC_8") (pintype "passive"))
      (node (ref "J19") (pin "2") (pinfunction "2_2") (pintype "passive"))
      (node (ref "J20") (pin "2") (pinfunction "2_2") (pintype "passive"))
      (node (ref "R172") (pin "1") (pinfunction "1_1") (pintype "passive"))
      (node (ref "R183") (pin "1") (pinfunction "1_1") (pintype "passive"))
      (node (ref "R188") (pin "1") (pinfunction "1_1") (pintype "passive"))
      (node (ref "R189") (pin "1") (pinfunction "1_1") (pintype "passive"))
      (node (ref "R190") (pin "1") (pinfunction "1_1") (pintype "passive"))
    )
    (net (code "58") (name "VCC_INT") (class "Default")
      (node (ref "R173") (pin "1") (pinfunction "1_1") (pintype "passive"))
    )
    (net (code "59") (name "VDIO_LMS_FPGA") (class "Default")
      (node (ref "C316") (pin "2") (pinfunction "2_2") (pintype "passive"))
      (node (ref "C317") (pin "2") (pinfunction "2_2") (pintype "passive"))
      (node (ref "C318") (pin "2") (pinfunction "2_2") (pintype "passive"))
      (node (ref "C319") (pin "2") (pinfunction "2_2") (pintype "passive"))
      (node (ref "C320") (pin "1") (pinfunction "1_1") (pintype "passive"))
      (node (ref "C332") (pin "1") (pinfunction "1_1") (pintype "passive"))
      (node (ref "C333") (pin "1") (pinfunction "1_1") (pintype "passive"))
      (node (ref "C334") (pin "1") (pinfunction "1_1") (pintype "passive"))
      (node (ref "C335") (pin "1") (pinfunction "1_1") (pintype "passive"))
      (node (ref "C336") (pin "1") (pinfunction "1_1") (pintype "passive"))
      (node (ref "C337") (pin "1") (pinfunction "1_1") (pintype "passive"))
      (node (ref "C338") (pin "1") (pinfunction "1_1") (pintype "passive"))
      (node (ref "C339") (pin "1") (pinfunction "1_1") (pintype "passive"))
      (node (ref "C340") (pin "1") (pinfunction "1_1") (pintype "passive"))
      (node (ref "C341") (pin "1") (pinfunction "1_1") (pintype "passive"))
      (node (ref "C342") (pin "1") (pinfunction "1_1") (pintype "passive"))
      (node (ref "C343") (pin "1") (pinfunction "1_1") (pintype "passive"))
      (node (ref "C344") (pin "1") (pinfunction "1_1") (pintype "passive"))
      (node (ref "C345") (pin "1") (pinfunction "1_1") (pintype "passive"))
      (node (ref "IC31") (pin "A2") (pinfunction "VCCIO8_A2") (pintype "power_in"))
      (node (ref "IC31") (pin "A21") (pinfunction "VCCIO7_A21") (pintype "power_in"))
      (node (ref "IC31") (pin "D11") (pinfunction "VCCIO8_D11") (pintype "power_in"))
      (node (ref "IC31") (pin "D12") (pinfunction "VCCIO7_D12") (pintype "power_in"))
      (node (ref "IC31") (pin "D14") (pinfunction "VCCIO7_D14") (pintype "power_in"))
      (node (ref "IC31") (pin "D16") (pinfunction "VCCIO7_D16") (pintype "power_in"))
      (node (ref "IC31") (pin "D18") (pinfunction "VCCIO7_D18") (pintype "power_in"))
      (node (ref "IC31") (pin "D5") (pinfunction "VCCIO8_D5") (pintype "power_in"))
      (node (ref "IC31") (pin "D9") (pinfunction "VCCIO8_D9") (pintype "power_in"))
      (node (ref "IC31") (pin "E19") (pinfunction "VCCIO6_E19") (pintype "power_in"))
      (node (ref "IC31") (pin "E8") (pinfunction "VCCIO8_E8") (pintype "power_in"))
      (node (ref "IC31") (pin "G19") (pinfunction "VCCIO6_G19") (pintype "power_in"))
      (node (ref "IC31") (pin "J20") (pinfunction "VCCIO6_J20") (pintype "power_in"))
      (node (ref "IC31") (pin "L19") (pinfunction "VCCIO6_L19") (pintype "power_in"))
    )
    (net (code "60") (name "unconnected-(J17-Pad6)") (class "Default")
      (node (ref "J17") (pin "6") (pinfunction "6_6") (pintype "passive+no_connect"))
    )
    (net (code "61") (name "unconnected-(J17-Pad7)") (class "Default")
      (node (ref "J17") (pin "7") (pinfunction "7_7") (pintype "passive+no_connect"))
    )
    (net (code "62") (name "unconnected-(J17-Pad8)") (class "Default")
      (node (ref "J17") (pin "8") (pinfunction "8_8") (pintype "passive+no_connect"))
    )
  )
)
